# motherboard.net
KiCad netlist of a schematic drawn in EAGLE
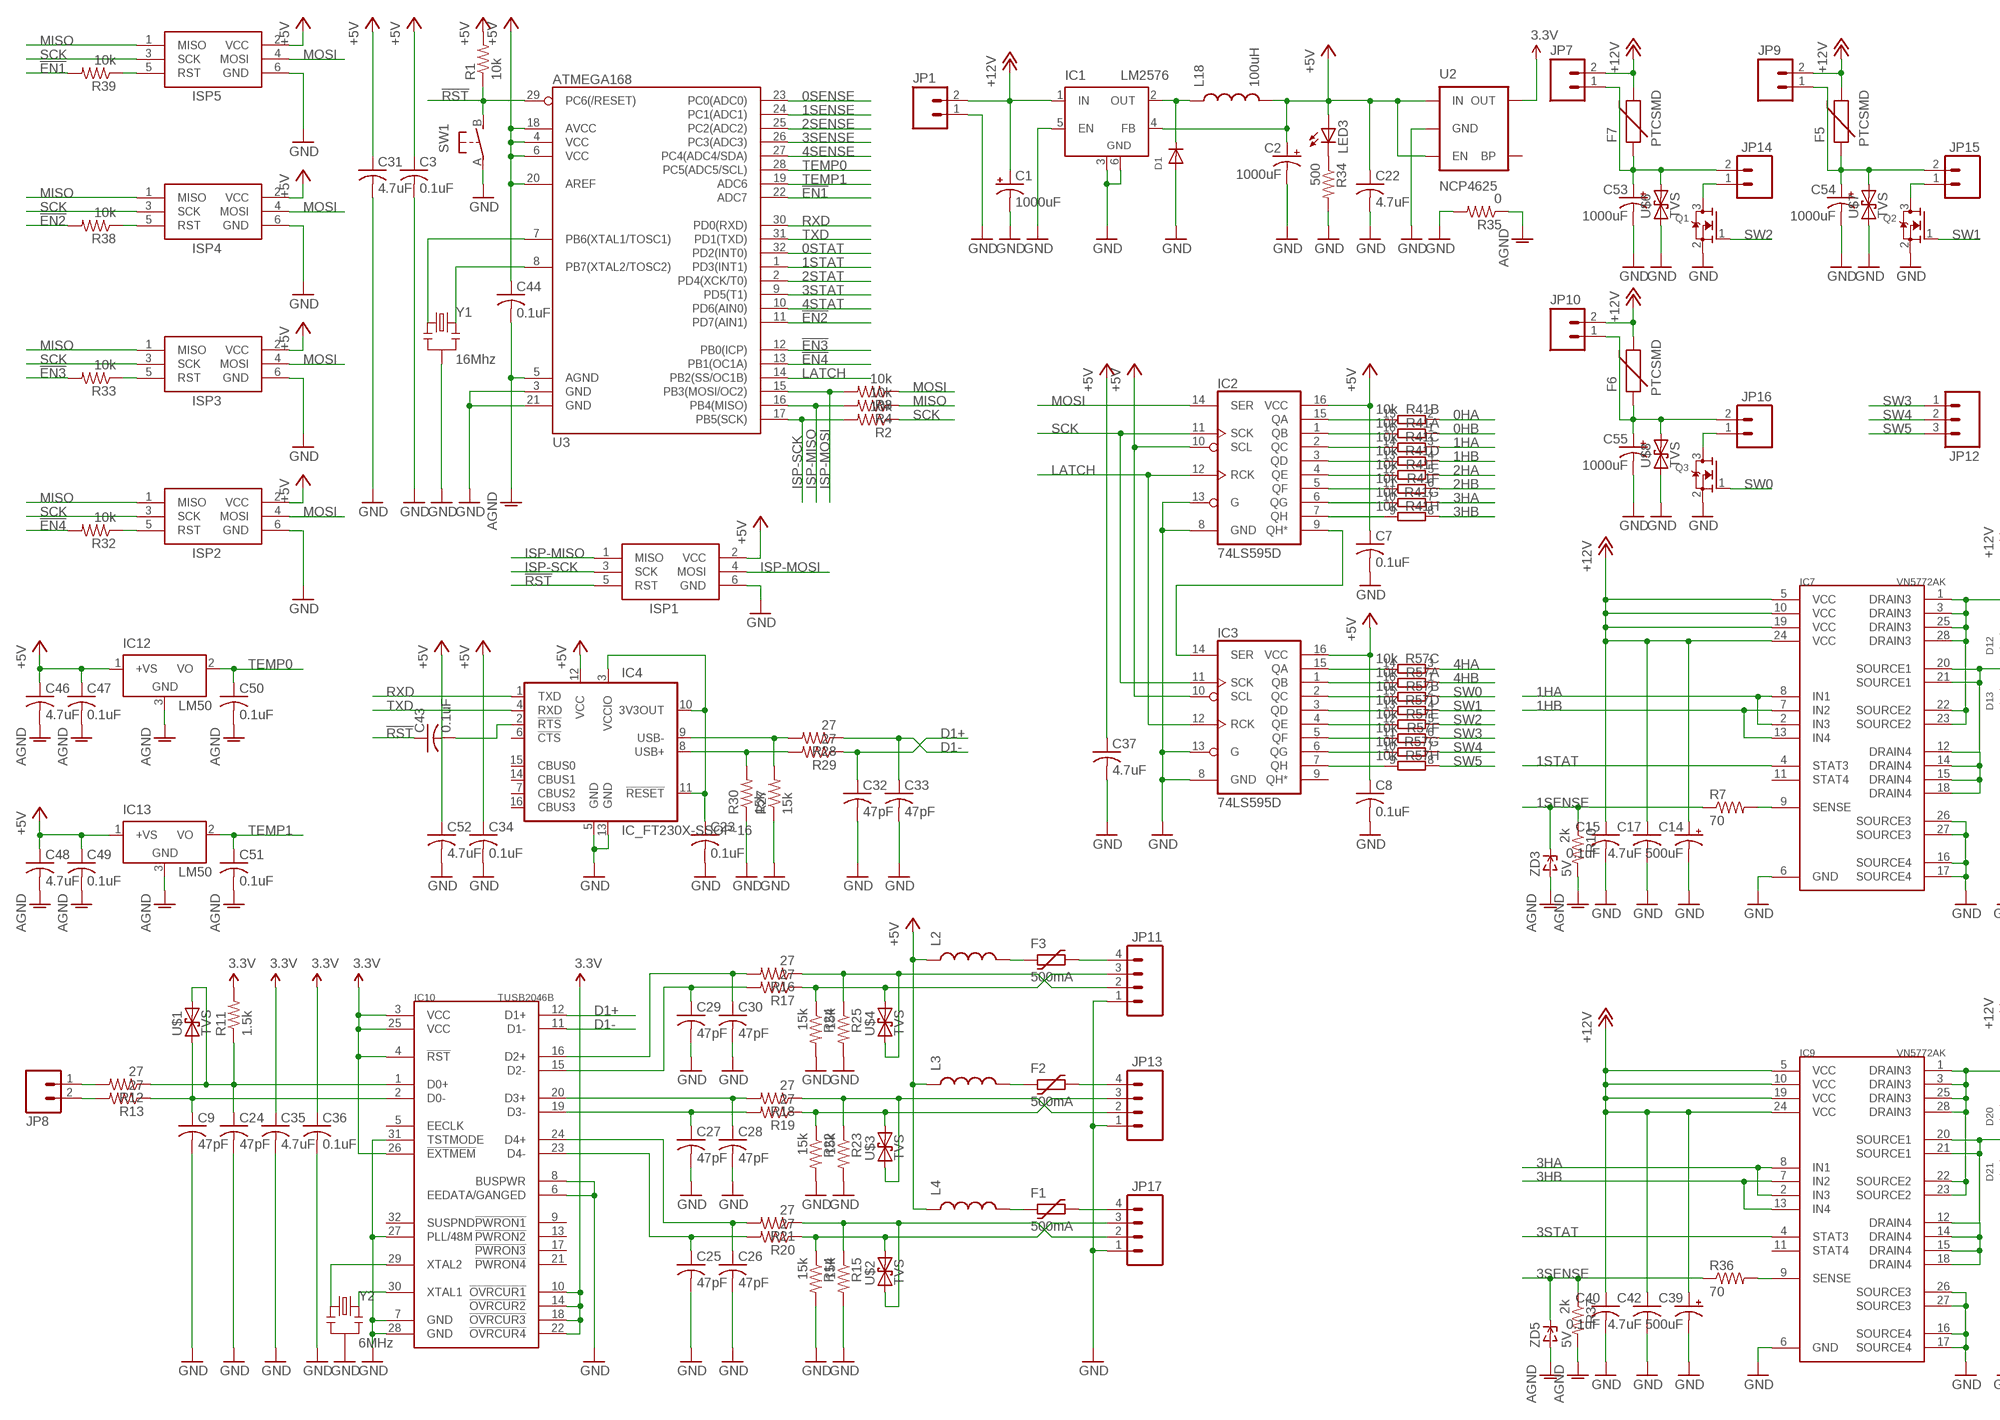
[diagram p0: schematic, sheet 1, part 1 of 2]
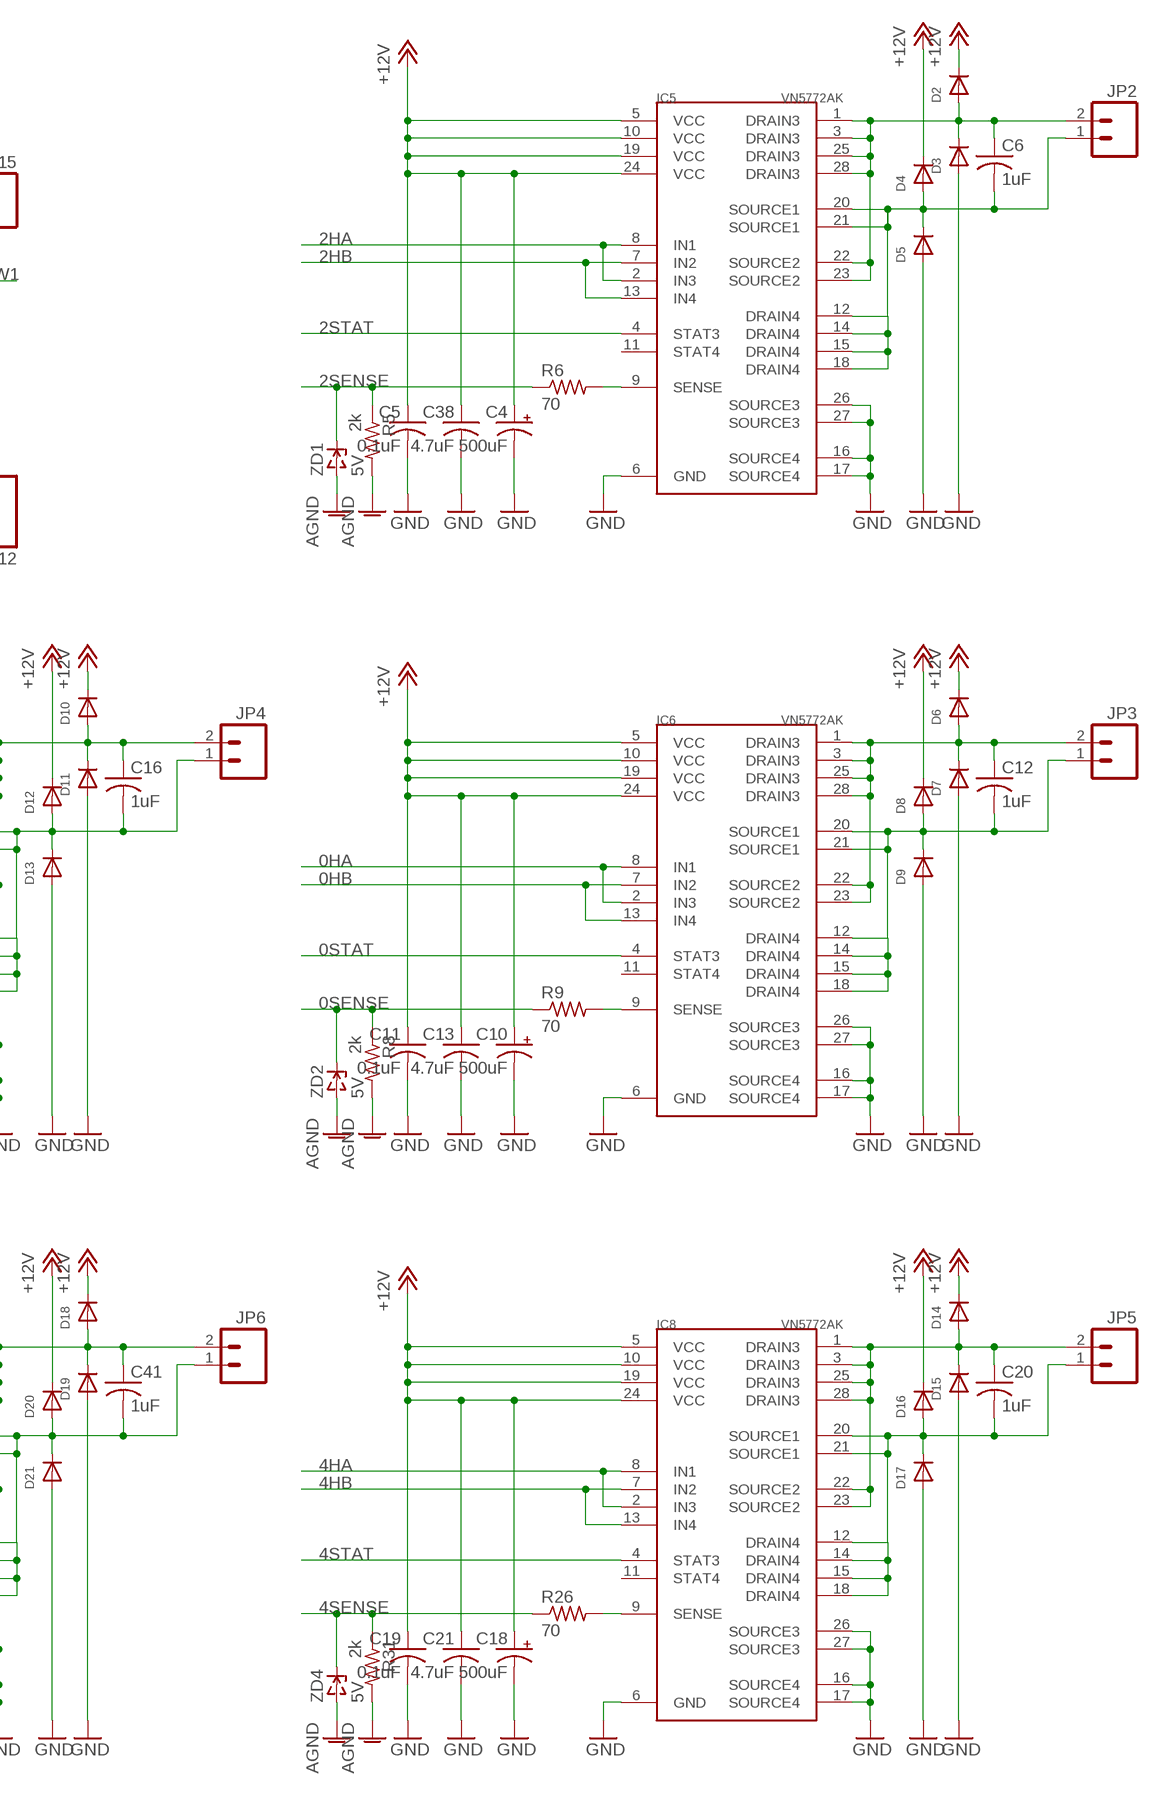
[diagram p1: schematic, sheet 1, part 2 of 2]

(export (version "E")
  (design (tool "Eeschema 10.0.6"))
  (components
    (comp (ref "C1")
      (value "1000uF")
      (footprint "eagle-import:153CLV-0807")
      (libsource (lib "eagle-import") (part "CPOL-US153CLV-0807"))
    )
    (comp (ref "C2")
      (value "1000uF")
      (footprint "eagle-import:153CLV-0807")
      (libsource (lib "eagle-import") (part "CPOL-US153CLV-0807"))
    )
    (comp (ref "C3")
      (value "0.1uF")
      (footprint "eagle-import:C1206")
      (libsource (lib "eagle-import") (part "C-USC1206"))
    )
    (comp (ref "C4")
      (value "500uF")
      (footprint "eagle-import:153CLV-0807")
      (libsource (lib "eagle-import") (part "CPOL-US153CLV-0807"))
    )
    (comp (ref "C5")
      (value "0.1uF")
      (footprint "eagle-import:C1206")
      (libsource (lib "eagle-import") (part "C-USC1206"))
    )
    (comp (ref "C6")
      (value "1uF")
      (footprint "eagle-import:C1206")
      (libsource (lib "eagle-import") (part "C-USC1206"))
    )
    (comp (ref "C7")
      (value "0.1uF")
      (footprint "eagle-import:C1206")
      (libsource (lib "eagle-import") (part "C-USC1206"))
    )
    (comp (ref "C8")
      (value "0.1uF")
      (footprint "eagle-import:C1206")
      (libsource (lib "eagle-import") (part "C-USC1206"))
    )
    (comp (ref "C9")
      (value "47pF")
      (footprint "eagle-import:C1206")
      (libsource (lib "eagle-import") (part "C-USC1206"))
    )
    (comp (ref "C10")
      (value "500uF")
      (footprint "eagle-import:153CLV-0807")
      (libsource (lib "eagle-import") (part "CPOL-US153CLV-0807"))
    )
    (comp (ref "C11")
      (value "0.1uF")
      (footprint "eagle-import:C1206")
      (libsource (lib "eagle-import") (part "C-USC1206"))
    )
    (comp (ref "C12")
      (value "1uF")
      (footprint "eagle-import:C1206")
      (libsource (lib "eagle-import") (part "C-USC1206"))
    )
    (comp (ref "C13")
      (value "4.7uF")
      (footprint "eagle-import:C1206")
      (libsource (lib "eagle-import") (part "C-USC1206"))
    )
    (comp (ref "C14")
      (value "500uF")
      (footprint "eagle-import:153CLV-0807")
      (libsource (lib "eagle-import") (part "CPOL-US153CLV-0807"))
    )
    (comp (ref "C15")
      (value "0.1uF")
      (footprint "eagle-import:C1206")
      (libsource (lib "eagle-import") (part "C-USC1206"))
    )
    (comp (ref "C16")
      (value "1uF")
      (footprint "eagle-import:C1206")
      (libsource (lib "eagle-import") (part "C-USC1206"))
    )
    (comp (ref "C17")
      (value "4.7uF")
      (footprint "eagle-import:C1206")
      (libsource (lib "eagle-import") (part "C-USC1206"))
    )
    (comp (ref "C18")
      (value "500uF")
      (footprint "eagle-import:153CLV-0807")
      (libsource (lib "eagle-import") (part "CPOL-US153CLV-0807"))
    )
    (comp (ref "C19")
      (value "0.1uF")
      (footprint "eagle-import:C1206")
      (libsource (lib "eagle-import") (part "C-USC1206"))
    )
    (comp (ref "C20")
      (value "1uF")
      (footprint "eagle-import:C1206")
      (libsource (lib "eagle-import") (part "C-USC1206"))
    )
    (comp (ref "C21")
      (value "4.7uF")
      (footprint "eagle-import:C1206")
      (libsource (lib "eagle-import") (part "C-USC1206"))
    )
    (comp (ref "C22")
      (value "4.7uF")
      (footprint "eagle-import:C1206")
      (libsource (lib "eagle-import") (part "C-USC1206"))
    )
    (comp (ref "C23")
      (value "0.1uF")
      (footprint "eagle-import:C1206")
      (libsource (lib "eagle-import") (part "C-USC1206"))
    )
    (comp (ref "C24")
      (value "47pF")
      (footprint "eagle-import:C1206")
      (libsource (lib "eagle-import") (part "C-USC1206"))
    )
    (comp (ref "C25")
      (value "47pF")
      (footprint "eagle-import:C1206")
      (libsource (lib "eagle-import") (part "C-USC1206"))
    )
    (comp (ref "C26")
      (value "47pF")
      (footprint "eagle-import:C1206")
      (libsource (lib "eagle-import") (part "C-USC1206"))
    )
    (comp (ref "C27")
      (value "47pF")
      (footprint "eagle-import:C1206")
      (libsource (lib "eagle-import") (part "C-USC1206"))
    )
    (comp (ref "C28")
      (value "47pF")
      (footprint "eagle-import:C1206")
      (libsource (lib "eagle-import") (part "C-USC1206"))
    )
    (comp (ref "C29")
      (value "47pF")
      (footprint "eagle-import:C1206")
      (libsource (lib "eagle-import") (part "C-USC1206"))
    )
    (comp (ref "C30")
      (value "47pF")
      (footprint "eagle-import:C1206")
      (libsource (lib "eagle-import") (part "C-USC1206"))
    )
    (comp (ref "C31")
      (value "4.7uF")
      (footprint "eagle-import:C1206")
      (libsource (lib "eagle-import") (part "C-USC1206"))
    )
    (comp (ref "C32")
      (value "47pF")
      (footprint "eagle-import:C1206")
      (libsource (lib "eagle-import") (part "C-USC1206"))
    )
    (comp (ref "C33")
      (value "47pF")
      (footprint "eagle-import:C1206")
      (libsource (lib "eagle-import") (part "C-USC1206"))
    )
    (comp (ref "C34")
      (value "0.1uF")
      (footprint "eagle-import:C1206")
      (libsource (lib "eagle-import") (part "C-USC1206"))
    )
    (comp (ref "C35")
      (value "4.7uF")
      (footprint "eagle-import:C1206")
      (libsource (lib "eagle-import") (part "C-USC1206"))
    )
    (comp (ref "C36")
      (value "0.1uF")
      (footprint "eagle-import:C1206")
      (libsource (lib "eagle-import") (part "C-USC1206"))
    )
    (comp (ref "C37")
      (value "4.7uF")
      (footprint "eagle-import:C1206")
      (libsource (lib "eagle-import") (part "C-USC1206"))
    )
    (comp (ref "C38")
      (value "4.7uF")
      (footprint "eagle-import:C1206")
      (libsource (lib "eagle-import") (part "C-USC1206"))
    )
    (comp (ref "C39")
      (value "500uF")
      (footprint "eagle-import:153CLV-0807")
      (libsource (lib "eagle-import") (part "CPOL-US153CLV-0807"))
    )
    (comp (ref "C40")
      (value "0.1uF")
      (footprint "eagle-import:C1206")
      (libsource (lib "eagle-import") (part "C-USC1206"))
    )
    (comp (ref "C41")
      (value "1uF")
      (footprint "eagle-import:C1206")
      (libsource (lib "eagle-import") (part "C-USC1206"))
    )
    (comp (ref "C42")
      (value "4.7uF")
      (footprint "eagle-import:C1206")
      (libsource (lib "eagle-import") (part "C-USC1206"))
    )
    (comp (ref "C43")
      (value "0.1uF")
      (footprint "eagle-import:C1206")
      (libsource (lib "eagle-import") (part "C-USC1206"))
    )
    (comp (ref "C44")
      (value "0.1uF")
      (footprint "eagle-import:C1206")
      (libsource (lib "eagle-import") (part "C-USC1206"))
    )
    (comp (ref "C46")
      (value "4.7uF")
      (footprint "eagle-import:C1206")
      (libsource (lib "eagle-import") (part "C-USC1206"))
    )
    (comp (ref "C47")
      (value "0.1uF")
      (footprint "eagle-import:C1206")
      (libsource (lib "eagle-import") (part "C-USC1206"))
    )
    (comp (ref "C48")
      (value "4.7uF")
      (footprint "eagle-import:C1206")
      (libsource (lib "eagle-import") (part "C-USC1206"))
    )
    (comp (ref "C49")
      (value "0.1uF")
      (footprint "eagle-import:C1206")
      (libsource (lib "eagle-import") (part "C-USC1206"))
    )
    (comp (ref "C50")
      (value "0.1uF")
      (footprint "eagle-import:C1206")
      (libsource (lib "eagle-import") (part "C-USC1206"))
    )
    (comp (ref "C51")
      (value "0.1uF")
      (footprint "eagle-import:C1206")
      (libsource (lib "eagle-import") (part "C-USC1206"))
    )
    (comp (ref "C52")
      (value "4.7uF")
      (footprint "eagle-import:C1206")
      (libsource (lib "eagle-import") (part "C-USC1206"))
    )
    (comp (ref "C53")
      (value "1000uF")
      (footprint "eagle-import:153CLV-0807")
      (libsource (lib "eagle-import") (part "CPOL-US153CLV-0807"))
    )
    (comp (ref "C54")
      (value "1000uF")
      (footprint "eagle-import:153CLV-0807")
      (libsource (lib "eagle-import") (part "CPOL-US153CLV-0807"))
    )
    (comp (ref "C55")
      (value "1000uF")
      (footprint "eagle-import:153CLV-0807")
      (libsource (lib "eagle-import") (part "CPOL-US153CLV-0807"))
    )
    (comp (ref "D1")
      (value "DIODESMA")
      (footprint "eagle-import:SMADIODE")
      (libsource (lib "eagle-import") (part "DIODESMA"))
    )
    (comp (ref "D2")
      (value "DIODESOD-123")
      (footprint "eagle-import:SOD-123")
      (libsource (lib "eagle-import") (part "DIODESOD-123"))
    )
    (comp (ref "D3")
      (value "DIODESOD-123")
      (footprint "eagle-import:SOD-123")
      (libsource (lib "eagle-import") (part "DIODESOD-123"))
    )
    (comp (ref "D4")
      (value "DIODESOD-123")
      (footprint "eagle-import:SOD-123")
      (libsource (lib "eagle-import") (part "DIODESOD-123"))
    )
    (comp (ref "D5")
      (value "DIODESOD-123")
      (footprint "eagle-import:SOD-123")
      (libsource (lib "eagle-import") (part "DIODESOD-123"))
    )
    (comp (ref "D6")
      (value "DIODESOD-123")
      (footprint "eagle-import:SOD-123")
      (libsource (lib "eagle-import") (part "DIODESOD-123"))
    )
    (comp (ref "D7")
      (value "DIODESOD-123")
      (footprint "eagle-import:SOD-123")
      (libsource (lib "eagle-import") (part "DIODESOD-123"))
    )
    (comp (ref "D8")
      (value "DIODESOD-123")
      (footprint "eagle-import:SOD-123")
      (libsource (lib "eagle-import") (part "DIODESOD-123"))
    )
    (comp (ref "D9")
      (value "DIODESOD-123")
      (footprint "eagle-import:SOD-123")
      (libsource (lib "eagle-import") (part "DIODESOD-123"))
    )
    (comp (ref "D10")
      (value "DIODESOD-123")
      (footprint "eagle-import:SOD-123")
      (libsource (lib "eagle-import") (part "DIODESOD-123"))
    )
    (comp (ref "D11")
      (value "DIODESOD-123")
      (footprint "eagle-import:SOD-123")
      (libsource (lib "eagle-import") (part "DIODESOD-123"))
    )
    (comp (ref "D12")
      (value "DIODESOD-123")
      (footprint "eagle-import:SOD-123")
      (libsource (lib "eagle-import") (part "DIODESOD-123"))
    )
    (comp (ref "D13")
      (value "DIODESOD-123")
      (footprint "eagle-import:SOD-123")
      (libsource (lib "eagle-import") (part "DIODESOD-123"))
    )
    (comp (ref "D14")
      (value "DIODESOD-123")
      (footprint "eagle-import:SOD-123")
      (libsource (lib "eagle-import") (part "DIODESOD-123"))
    )
    (comp (ref "D15")
      (value "DIODESOD-123")
      (footprint "eagle-import:SOD-123")
      (libsource (lib "eagle-import") (part "DIODESOD-123"))
    )
    (comp (ref "D16")
      (value "DIODESOD-123")
      (footprint "eagle-import:SOD-123")
      (libsource (lib "eagle-import") (part "DIODESOD-123"))
    )
    (comp (ref "D17")
      (value "DIODESOD-123")
      (footprint "eagle-import:SOD-123")
      (libsource (lib "eagle-import") (part "DIODESOD-123"))
    )
    (comp (ref "D18")
      (value "DIODESOD-123")
      (footprint "eagle-import:SOD-123")
      (libsource (lib "eagle-import") (part "DIODESOD-123"))
    )
    (comp (ref "D19")
      (value "DIODESOD-123")
      (footprint "eagle-import:SOD-123")
      (libsource (lib "eagle-import") (part "DIODESOD-123"))
    )
    (comp (ref "D20")
      (value "DIODESOD-123")
      (footprint "eagle-import:SOD-123")
      (libsource (lib "eagle-import") (part "DIODESOD-123"))
    )
    (comp (ref "D21")
      (value "DIODESOD-123")
      (footprint "eagle-import:SOD-123")
      (libsource (lib "eagle-import") (part "DIODESOD-123"))
    )
    (comp (ref "F1")
      (value "500mA")
      (footprint "eagle-import:PTC1812L")
      (libsource (lib "eagle-import") (part "FUSE_PTC-1812"))
    )
    (comp (ref "F2")
      (value "500mA")
      (footprint "eagle-import:PTC1812L")
      (libsource (lib "eagle-import") (part "FUSE_PTC-1812"))
    )
    (comp (ref "F3")
      (value "500mA")
      (footprint "eagle-import:PTC1812L")
      (libsource (lib "eagle-import") (part "FUSE_PTC-1812"))
    )
    (comp (ref "F5")
      (value "PTCSMD")
      (footprint "eagle-import:PTC-1206")
      (libsource (lib "eagle-import") (part "PTCSMD"))
    )
    (comp (ref "F6")
      (value "PTCSMD")
      (footprint "eagle-import:PTC-1206")
      (libsource (lib "eagle-import") (part "PTCSMD"))
    )
    (comp (ref "F7")
      (value "PTCSMD")
      (footprint "eagle-import:PTC-1206")
      (libsource (lib "eagle-import") (part "PTCSMD"))
    )
    (comp (ref "IC1")
      (value "LM2576")
      (footprint "eagle-import:TO263-5")
      (libsource (lib "eagle-import") (part "LM2596S"))
    )
    (comp (ref "IC2")
      (value "74LS595D")
      (footprint "eagle-import:SO16")
      (libsource (lib "eagle-import") (part "74595DLS"))
    )
    (comp (ref "IC3")
      (value "74LS595D")
      (footprint "eagle-import:SO16")
      (libsource (lib "eagle-import") (part "74595DLS"))
    )
    (comp (ref "IC4")
      (value "IC_FT230X-SSOP-16")
      (footprint "eagle-import:SSOP-16-FTDI")
      (libsource (lib "eagle-import") (part "IC_FT230X-SSOP-16"))
    )
    (comp (ref "IC5")
      (value "VN5772AK")
      (footprint "eagle-import:SO-28")
      (libsource (lib "eagle-import") (part "VN5772AK"))
    )
    (comp (ref "IC6")
      (value "VN5772AK")
      (footprint "eagle-import:SO-28")
      (libsource (lib "eagle-import") (part "VN5772AK"))
    )
    (comp (ref "IC7")
      (value "VN5772AK")
      (footprint "eagle-import:SO-28")
      (libsource (lib "eagle-import") (part "VN5772AK"))
    )
    (comp (ref "IC8")
      (value "VN5772AK")
      (footprint "eagle-import:SO-28")
      (libsource (lib "eagle-import") (part "VN5772AK"))
    )
    (comp (ref "IC9")
      (value "VN5772AK")
      (footprint "eagle-import:SO-28")
      (libsource (lib "eagle-import") (part "VN5772AK"))
    )
    (comp (ref "IC10")
      (value "TUSB2046B")
      (footprint "eagle-import:LQFP-32")
      (libsource (lib "eagle-import") (part "TUSB2046B"))
    )
    (comp (ref "IC12")
      (value "LM50")
      (footprint "eagle-import:SOT23")
      (libsource (lib "eagle-import") (part "LM50"))
    )
    (comp (ref "IC13")
      (value "LM50")
      (footprint "eagle-import:SOT23")
      (libsource (lib "eagle-import") (part "LM50"))
    )
    (comp (ref "ISP1")
      (value "AVRISP-6")
      (footprint "eagle-import:AVRISP")
      (libsource (lib "eagle-import") (part "AVRISP-6"))
    )
    (comp (ref "ISP2")
      (value "AVRISP-6")
      (footprint "eagle-import:AVRISP")
      (libsource (lib "eagle-import") (part "AVRISP-6"))
    )
    (comp (ref "ISP3")
      (value "AVRISP-6")
      (footprint "eagle-import:AVRISP")
      (libsource (lib "eagle-import") (part "AVRISP-6"))
    )
    (comp (ref "ISP4")
      (value "AVRISP-6")
      (footprint "eagle-import:AVRISP")
      (libsource (lib "eagle-import") (part "AVRISP-6"))
    )
    (comp (ref "ISP5")
      (value "AVRISP-6")
      (footprint "eagle-import:AVRISP")
      (libsource (lib "eagle-import") (part "AVRISP-6"))
    )
    (comp (ref "JP1")
      (value "M023.5MM")
      (footprint "eagle-import:SCREWTERMINAL-3.5MM-2")
      (libsource (lib "eagle-import") (part "M023.5MM"))
    )
    (comp (ref "JP2")
      (value "M023.5MM")
      (footprint "eagle-import:SCREWTERMINAL-3.5MM-2")
      (libsource (lib "eagle-import") (part "M023.5MM"))
    )
    (comp (ref "JP3")
      (value "M023.5MM")
      (footprint "eagle-import:SCREWTERMINAL-3.5MM-2")
      (libsource (lib "eagle-import") (part "M023.5MM"))
    )
    (comp (ref "JP4")
      (value "M023.5MM")
      (footprint "eagle-import:SCREWTERMINAL-3.5MM-2")
      (libsource (lib "eagle-import") (part "M023.5MM"))
    )
    (comp (ref "JP5")
      (value "M023.5MM")
      (footprint "eagle-import:SCREWTERMINAL-3.5MM-2")
      (libsource (lib "eagle-import") (part "M023.5MM"))
    )
    (comp (ref "JP6")
      (value "M023.5MM")
      (footprint "eagle-import:SCREWTERMINAL-3.5MM-2")
      (libsource (lib "eagle-import") (part "M023.5MM"))
    )
    (comp (ref "JP7")
      (value "M02PTH")
      (footprint "eagle-import:1X02")
      (libsource (lib "eagle-import") (part "M02PTH"))
    )
    (comp (ref "JP8")
      (value "M023.5MM")
      (footprint "eagle-import:SCREWTERMINAL-3.5MM-2")
      (libsource (lib "eagle-import") (part "M023.5MM"))
    )
    (comp (ref "JP9")
      (value "M02PTH")
      (footprint "eagle-import:1X02")
      (libsource (lib "eagle-import") (part "M02PTH"))
    )
    (comp (ref "JP10")
      (value "M02PTH")
      (footprint "eagle-import:1X02")
      (libsource (lib "eagle-import") (part "M02PTH"))
    )
    (comp (ref "JP11")
      (value "M04SCREW")
      (footprint "eagle-import:SCREWTERMINAL-3.5MM-4")
      (libsource (lib "eagle-import") (part "M04SCREW"))
    )
    (comp (ref "JP12")
      (value "M03PTH")
      (footprint "eagle-import:1X03")
      (libsource (lib "eagle-import") (part "M03PTH"))
    )
    (comp (ref "JP13")
      (value "M04SCREW")
      (footprint "eagle-import:SCREWTERMINAL-3.5MM-4")
      (libsource (lib "eagle-import") (part "M04SCREW"))
    )
    (comp (ref "JP14")
      (value "M023.5MM")
      (footprint "eagle-import:SCREWTERMINAL-3.5MM-2")
      (libsource (lib "eagle-import") (part "M023.5MM"))
    )
    (comp (ref "JP15")
      (value "M023.5MM")
      (footprint "eagle-import:SCREWTERMINAL-3.5MM-2")
      (libsource (lib "eagle-import") (part "M023.5MM"))
    )
    (comp (ref "JP16")
      (value "M023.5MM")
      (footprint "eagle-import:SCREWTERMINAL-3.5MM-2")
      (libsource (lib "eagle-import") (part "M023.5MM"))
    )
    (comp (ref "JP17")
      (value "M04SCREW")
      (footprint "eagle-import:SCREWTERMINAL-3.5MM-4")
      (libsource (lib "eagle-import") (part "M04SCREW"))
    )
    (comp (ref "L2")
      (value "INDUCTOR1206H*")
      (footprint "eagle-import:INDUCTOR-1206")
      (libsource (lib "eagle-import") (part "INDUCTORH1206"))
    )
    (comp (ref "L3")
      (value "INDUCTOR1206H*")
      (footprint "eagle-import:INDUCTOR-1206")
      (libsource (lib "eagle-import") (part "INDUCTORH1206"))
    )
    (comp (ref "L4")
      (value "INDUCTOR1206H*")
      (footprint "eagle-import:INDUCTOR-1206")
      (libsource (lib "eagle-import") (part "INDUCTORH1206"))
    )
    (comp (ref "L18")
      (value "100uH")
      (footprint "eagle-import:CDRH125")
      (libsource (lib "eagle-import") (part "INDUCTORPWR"))
    )
    (comp (ref "LED3")
      (value "LEDCHIPLED_1206")
      (footprint "eagle-import:CHIPLED_1206")
      (libsource (lib "eagle-import") (part "LEDCHIPLED_1206"))
    )
    (comp (ref "Q1")
      (value "MOSFET-NREFLOW")
      (footprint "eagle-import:SOT23")
      (libsource (lib "eagle-import") (part "MOSFET-NREFLOW"))
    )
    (comp (ref "Q2")
      (value "MOSFET-NREFLOW")
      (footprint "eagle-import:SOT23")
      (libsource (lib "eagle-import") (part "MOSFET-NREFLOW"))
    )
    (comp (ref "Q3")
      (value "MOSFET-NREFLOW")
      (footprint "eagle-import:SOT23")
      (libsource (lib "eagle-import") (part "MOSFET-NREFLOW"))
    )
    (comp (ref "R1")
      (value "10k")
      (footprint "eagle-import:R1206")
      (libsource (lib "eagle-import") (part "R-US_R1206"))
    )
    (comp (ref "R2")
      (value "10k")
      (footprint "eagle-import:R1206")
      (libsource (lib "eagle-import") (part "R-US_R1206"))
    )
    (comp (ref "R3")
      (value "10k")
      (footprint "eagle-import:R1206")
      (libsource (lib "eagle-import") (part "R-US_R1206"))
    )
    (comp (ref "R4")
      (value "10k")
      (footprint "eagle-import:R1206")
      (libsource (lib "eagle-import") (part "R-US_R1206"))
    )
    (comp (ref "R5")
      (value "2k")
      (footprint "eagle-import:R1206")
      (libsource (lib "eagle-import") (part "R-US_R1206"))
    )
    (comp (ref "R6")
      (value "70")
      (footprint "eagle-import:R1206")
      (libsource (lib "eagle-import") (part "R-US_R1206"))
    )
    (comp (ref "R7")
      (value "70")
      (footprint "eagle-import:R1206")
      (libsource (lib "eagle-import") (part "R-US_R1206"))
    )
    (comp (ref "R8")
      (value "2k")
      (footprint "eagle-import:R1206")
      (libsource (lib "eagle-import") (part "R-US_R1206"))
    )
    (comp (ref "R9")
      (value "70")
      (footprint "eagle-import:R1206")
      (libsource (lib "eagle-import") (part "R-US_R1206"))
    )
    (comp (ref "R10")
      (value "2k")
      (footprint "eagle-import:R1206")
      (libsource (lib "eagle-import") (part "R-US_R1206"))
    )
    (comp (ref "R11")
      (value "1.5k")
      (footprint "eagle-import:R1206")
      (libsource (lib "eagle-import") (part "R-US_R1206"))
    )
    (comp (ref "R12")
      (value "27")
      (footprint "eagle-import:R1206")
      (libsource (lib "eagle-import") (part "R-US_R1206"))
    )
    (comp (ref "R13")
      (value "27")
      (footprint "eagle-import:R1206")
      (libsource (lib "eagle-import") (part "R-US_R1206"))
    )
    (comp (ref "R14")
      (value "15k")
      (footprint "eagle-import:R1206")
      (libsource (lib "eagle-import") (part "R-US_R1206"))
    )
    (comp (ref "R15")
      (value "15k")
      (footprint "eagle-import:R1206")
      (libsource (lib "eagle-import") (part "R-US_R1206"))
    )
    (comp (ref "R16")
      (value "27")
      (footprint "eagle-import:R1206")
      (libsource (lib "eagle-import") (part "R-US_R1206"))
    )
    (comp (ref "R17")
      (value "27")
      (footprint "eagle-import:R1206")
      (libsource (lib "eagle-import") (part "R-US_R1206"))
    )
    (comp (ref "R18")
      (value "27")
      (footprint "eagle-import:R1206")
      (libsource (lib "eagle-import") (part "R-US_R1206"))
    )
    (comp (ref "R19")
      (value "27")
      (footprint "eagle-import:R1206")
      (libsource (lib "eagle-import") (part "R-US_R1206"))
    )
    (comp (ref "R20")
      (value "27")
      (footprint "eagle-import:R1206")
      (libsource (lib "eagle-import") (part "R-US_R1206"))
    )
    (comp (ref "R21")
      (value "27")
      (footprint "eagle-import:R1206")
      (libsource (lib "eagle-import") (part "R-US_R1206"))
    )
    (comp (ref "R22")
      (value "15k")
      (footprint "eagle-import:R1206")
      (libsource (lib "eagle-import") (part "R-US_R1206"))
    )
    (comp (ref "R23")
      (value "15k")
      (footprint "eagle-import:R1206")
      (libsource (lib "eagle-import") (part "R-US_R1206"))
    )
    (comp (ref "R24")
      (value "15k")
      (footprint "eagle-import:R1206")
      (libsource (lib "eagle-import") (part "R-US_R1206"))
    )
    (comp (ref "R25")
      (value "15k")
      (footprint "eagle-import:R1206")
      (libsource (lib "eagle-import") (part "R-US_R1206"))
    )
    (comp (ref "R26")
      (value "70")
      (footprint "eagle-import:R1206")
      (libsource (lib "eagle-import") (part "R-US_R1206"))
    )
    (comp (ref "R27")
      (value "15k")
      (footprint "eagle-import:R1206")
      (libsource (lib "eagle-import") (part "R-US_R1206"))
    )
    (comp (ref "R28")
      (value "27")
      (footprint "eagle-import:R1206")
      (libsource (lib "eagle-import") (part "R-US_R1206"))
    )
    (comp (ref "R29")
      (value "27")
      (footprint "eagle-import:R1206")
      (libsource (lib "eagle-import") (part "R-US_R1206"))
    )
    (comp (ref "R30")
      (value "15k")
      (footprint "eagle-import:R1206")
      (libsource (lib "eagle-import") (part "R-US_R1206"))
    )
    (comp (ref "R31")
      (value "2k")
      (footprint "eagle-import:R1206")
      (libsource (lib "eagle-import") (part "R-US_R1206"))
    )
    (comp (ref "R32")
      (value "10k")
      (footprint "eagle-import:R1206")
      (libsource (lib "eagle-import") (part "R-US_R1206"))
    )
    (comp (ref "R33")
      (value "10k")
      (footprint "eagle-import:R1206")
      (libsource (lib "eagle-import") (part "R-US_R1206"))
    )
    (comp (ref "R34")
      (value "500")
      (footprint "eagle-import:R1206")
      (libsource (lib "eagle-import") (part "R-US_R1206"))
    )
    (comp (ref "R35")
      (value "0")
      (footprint "eagle-import:R1206")
      (libsource (lib "eagle-import") (part "R-US_R1206"))
    )
    (comp (ref "R36")
      (value "70")
      (footprint "eagle-import:R1206")
      (libsource (lib "eagle-import") (part "R-US_R1206"))
    )
    (comp (ref "R37")
      (value "2k")
      (footprint "eagle-import:R1206")
      (libsource (lib "eagle-import") (part "R-US_R1206"))
    )
    (comp (ref "R38")
      (value "10k")
      (footprint "eagle-import:R1206")
      (libsource (lib "eagle-import") (part "R-US_R1206"))
    )
    (comp (ref "R39")
      (value "10k")
      (footprint "eagle-import:R1206")
      (libsource (lib "eagle-import") (part "R-US_R1206"))
    )
    (comp (ref "R41")
      (value "10k")
      (footprint "eagle-import:SO16")
      (libsource (lib "eagle-import") (part "2NBS16-8E"))
    )
    (comp (ref "R57")
      (value "10k")
      (footprint "eagle-import:SO16")
      (libsource (lib "eagle-import") (part "2NBS16-8E"))
    )
    (comp (ref "SW1")
      (value "FSMSM")
      (footprint "eagle-import:FSMSM")
      (libsource (lib "eagle-import") (part "FSMSM"))
    )
    (comp (ref "U$1")
      (value "TVS")
      (footprint "eagle-import:SMA-DIODE")
      (libsource (lib "eagle-import") (part "TVS"))
    )
    (comp (ref "U$2")
      (value "TVS")
      (footprint "eagle-import:SMA-DIODE")
      (libsource (lib "eagle-import") (part "TVS"))
    )
    (comp (ref "U$3")
      (value "TVS")
      (footprint "eagle-import:SMA-DIODE")
      (libsource (lib "eagle-import") (part "TVS"))
    )
    (comp (ref "U$4")
      (value "TVS")
      (footprint "eagle-import:SMA-DIODE")
      (libsource (lib "eagle-import") (part "TVS"))
    )
    (comp (ref "U$6")
      (value "TVS")
      (footprint "eagle-import:SMA-DIODE")
      (libsource (lib "eagle-import") (part "TVS"))
    )
    (comp (ref "U$7")
      (value "TVS")
      (footprint "eagle-import:SMA-DIODE")
      (libsource (lib "eagle-import") (part "TVS"))
    )
    (comp (ref "U$8")
      (value "TVS")
      (footprint "eagle-import:SMA-DIODE")
      (libsource (lib "eagle-import") (part "TVS"))
    )
    (comp (ref "U2")
      (value "NCP4625")
      (footprint "eagle-import:SOT23-5")
      (libsource (lib "eagle-import") (part "V_REG_LDOSMD"))
    )
    (comp (ref "U3")
      (value "ATMEGA168")
      (footprint "eagle-import:TQFP32-08")
      (libsource (lib "eagle-import") (part "ATMEGA168"))
    )
    (comp (ref "Y1")
      (value "16Mhz")
      (footprint "eagle-import:RESONATOR-SMD")
      (libsource (lib "eagle-import") (part "RESONATORSMD"))
    )
    (comp (ref "Y2")
      (value "6MHz")
      (footprint "eagle-import:RESONATOR-SMD")
      (libsource (lib "eagle-import") (part "RESONATORSMD"))
    )
    (comp (ref "ZD1")
      (value "5V")
      (footprint "eagle-import:SOD-123")
      (libsource (lib "eagle-import") (part "ZENERSOD-123"))
    )
    (comp (ref "ZD2")
      (value "5V")
      (footprint "eagle-import:SOD-123")
      (libsource (lib "eagle-import") (part "ZENERSOD-123"))
    )
    (comp (ref "ZD3")
      (value "5V")
      (footprint "eagle-import:SOD-123")
      (libsource (lib "eagle-import") (part "ZENERSOD-123"))
    )
    (comp (ref "ZD4")
      (value "5V")
      (footprint "eagle-import:SOD-123")
      (libsource (lib "eagle-import") (part "ZENERSOD-123"))
    )
    (comp (ref "ZD5")
      (value "5V")
      (footprint "eagle-import:SOD-123")
      (libsource (lib "eagle-import") (part "ZENERSOD-123"))
    )
  )
  (nets
    (net (code "1") (name "+5V") (class "Default")
      (node (ref "C2") (pin "+") (pinfunction "+_+") (pintype "passive"))
      (node (ref "C22") (pin "1") (pinfunction "1_1") (pintype "passive"))
      (node (ref "C3") (pin "1") (pinfunction "1_1") (pintype "passive"))
      (node (ref "C31") (pin "1") (pinfunction "1_1") (pintype "passive"))
      (node (ref "C34") (pin "1") (pinfunction "1_1") (pintype "passive"))
      (node (ref "C37") (pin "1") (pinfunction "1_1") (pintype "passive"))
      (node (ref "C44") (pin "1") (pinfunction "1_1") (pintype "passive"))
      (node (ref "C46") (pin "1") (pinfunction "1_1") (pintype "passive"))
      (node (ref "C47") (pin "1") (pinfunction "1_1") (pintype "passive"))
      (node (ref "C48") (pin "1") (pinfunction "1_1") (pintype "passive"))
      (node (ref "C49") (pin "1") (pinfunction "1_1") (pintype "passive"))
      (node (ref "C52") (pin "1") (pinfunction "1_1") (pintype "passive"))
      (node (ref "C7") (pin "1") (pinfunction "1_1") (pintype "passive"))
      (node (ref "C8") (pin "1") (pinfunction "1_1") (pintype "passive"))
      (node (ref "IC1") (pin "4") (pinfunction "FB_4") (pintype "input"))
      (node (ref "IC12") (pin "1") (pinfunction "+VS_1") (pintype "input"))
      (node (ref "IC13") (pin "1") (pinfunction "+VS_1") (pintype "input"))
      (node (ref "IC2") (pin "10") (pinfunction "SCL_10") (pintype "input"))
      (node (ref "IC2") (pin "16") (pinfunction "VCC_16") (pintype "power_in"))
      (node (ref "IC3") (pin "10") (pinfunction "SCL_10") (pintype "input"))
      (node (ref "IC3") (pin "16") (pinfunction "VCC_16") (pintype "power_in"))
      (node (ref "IC4") (pin "12") (pinfunction "VCC_12") (pintype "power_in"))
      (node (ref "ISP1") (pin "2") (pinfunction "VCC_2") (pintype "power_in"))
      (node (ref "ISP2") (pin "2") (pinfunction "VCC_2") (pintype "power_in"))
      (node (ref "ISP3") (pin "2") (pinfunction "VCC_2") (pintype "power_in"))
      (node (ref "ISP4") (pin "2") (pinfunction "VCC_2") (pintype "power_in"))
      (node (ref "ISP5") (pin "2") (pinfunction "VCC_2") (pintype "power_in"))
      (node (ref "L18") (pin "2") (pinfunction "2_2") (pintype "passive"))
      (node (ref "L2") (pin "P$1") (pinfunction "1_P$1") (pintype "passive"))
      (node (ref "L3") (pin "P$1") (pinfunction "1_P$1") (pintype "passive"))
      (node (ref "L4") (pin "P$1") (pinfunction "1_P$1") (pintype "passive"))
      (node (ref "LED3") (pin "A") (pinfunction "A_A") (pintype "passive"))
      (node (ref "R1") (pin "2") (pinfunction "2_2") (pintype "passive"))
      (node (ref "U2") (pin "1") (pinfunction "IN_1") (pintype "input"))
      (node (ref "U2") (pin "3") (pinfunction "EN_3") (pintype "input"))
      (node (ref "U3") (pin "18") (pinfunction "AVCC_18") (pintype "bidirectional"))
      (node (ref "U3") (pin "20") (pinfunction "AREF_20") (pintype "bidirectional"))
      (node (ref "U3") (pin "4") (pinfunction "VCC_4") (pintype "bidirectional"))
      (node (ref "U3") (pin "6") (pinfunction "VCC_6") (pintype "bidirectional"))
    )
    (net (code "2") (name "+12V") (class "Default")
      (node (ref "C1") (pin "+") (pinfunction "+_+") (pintype "passive"))
      (node (ref "C10") (pin "+") (pinfunction "+_+") (pintype "passive"))
      (node (ref "C11") (pin "1") (pinfunction "1_1") (pintype "passive"))
      (node (ref "C13") (pin "1") (pinfunction "1_1") (pintype "passive"))
      (node (ref "C14") (pin "+") (pinfunction "+_+") (pintype "passive"))
      (node (ref "C15") (pin "1") (pinfunction "1_1") (pintype "passive"))
      (node (ref "C17") (pin "1") (pinfunction "1_1") (pintype "passive"))
      (node (ref "C18") (pin "+") (pinfunction "+_+") (pintype "passive"))
      (node (ref "C19") (pin "1") (pinfunction "1_1") (pintype "passive"))
      (node (ref "C21") (pin "1") (pinfunction "1_1") (pintype "passive"))
      (node (ref "C38") (pin "1") (pinfunction "1_1") (pintype "passive"))
      (node (ref "C39") (pin "+") (pinfunction "+_+") (pintype "passive"))
      (node (ref "C4") (pin "+") (pinfunction "+_+") (pintype "passive"))
      (node (ref "C40") (pin "1") (pinfunction "1_1") (pintype "passive"))
      (node (ref "C42") (pin "1") (pinfunction "1_1") (pintype "passive"))
      (node (ref "C5") (pin "1") (pinfunction "1_1") (pintype "passive"))
      (node (ref "D10") (pin "C") (pinfunction "C_C") (pintype "passive"))
      (node (ref "D12") (pin "C") (pinfunction "C_C") (pintype "passive"))
      (node (ref "D14") (pin "C") (pinfunction "C_C") (pintype "passive"))
      (node (ref "D16") (pin "C") (pinfunction "C_C") (pintype "passive"))
      (node (ref "D18") (pin "C") (pinfunction "C_C") (pintype "passive"))
      (node (ref "D2") (pin "C") (pinfunction "C_C") (pintype "passive"))
      (node (ref "D20") (pin "C") (pinfunction "C_C") (pintype "passive"))
      (node (ref "D4") (pin "C") (pinfunction "C_C") (pintype "passive"))
      (node (ref "D6") (pin "C") (pinfunction "C_C") (pintype "passive"))
      (node (ref "D8") (pin "C") (pinfunction "C_C") (pintype "passive"))
      (node (ref "F5") (pin "2") (pinfunction "2_2") (pintype "bidirectional"))
      (node (ref "F6") (pin "2") (pinfunction "2_2") (pintype "bidirectional"))
      (node (ref "F7") (pin "2") (pinfunction "2_2") (pintype "bidirectional"))
      (node (ref "IC1") (pin "1") (pinfunction "IN_1") (pintype "input"))
      (node (ref "IC5") (pin "10") (pinfunction "VCC_10") (pintype "bidirectional"))
      (node (ref "IC5") (pin "19") (pinfunction "VCC_19") (pintype "bidirectional"))
      (node (ref "IC5") (pin "24") (pinfunction "VCC_24") (pintype "bidirectional"))
      (node (ref "IC5") (pin "5") (pinfunction "VCC_5") (pintype "bidirectional"))
      (node (ref "IC6") (pin "10") (pinfunction "VCC_10") (pintype "bidirectional"))
      (node (ref "IC6") (pin "19") (pinfunction "VCC_19") (pintype "bidirectional"))
      (node (ref "IC6") (pin "24") (pinfunction "VCC_24") (pintype "bidirectional"))
      (node (ref "IC6") (pin "5") (pinfunction "VCC_5") (pintype "bidirectional"))
      (node (ref "IC7") (pin "10") (pinfunction "VCC_10") (pintype "bidirectional"))
      (node (ref "IC7") (pin "19") (pinfunction "VCC_19") (pintype "bidirectional"))
      (node (ref "IC7") (pin "24") (pinfunction "VCC_24") (pintype "bidirectional"))
      (node (ref "IC7") (pin "5") (pinfunction "VCC_5") (pintype "bidirectional"))
      (node (ref "IC8") (pin "10") (pinfunction "VCC_10") (pintype "bidirectional"))
      (node (ref "IC8") (pin "19") (pinfunction "VCC_19") (pintype "bidirectional"))
      (node (ref "IC8") (pin "24") (pinfunction "VCC_24") (pintype "bidirectional"))
      (node (ref "IC8") (pin "5") (pinfunction "VCC_5") (pintype "bidirectional"))
      (node (ref "IC9") (pin "10") (pinfunction "VCC_10") (pintype "bidirectional"))
      (node (ref "IC9") (pin "19") (pinfunction "VCC_19") (pintype "bidirectional"))
      (node (ref "IC9") (pin "24") (pinfunction "VCC_24") (pintype "bidirectional"))
      (node (ref "IC9") (pin "5") (pinfunction "VCC_5") (pintype "bidirectional"))
      (node (ref "JP1") (pin "2") (pinfunction "2_2") (pintype "passive"))
      (node (ref "JP10") (pin "2") (pinfunction "2_2") (pintype "passive"))
      (node (ref "JP7") (pin "2") (pinfunction "2_2") (pintype "passive"))
      (node (ref "JP9") (pin "2") (pinfunction "2_2") (pintype "passive"))
    )
    (net (code "3") (name "/0HA") (class "Default")
      (node (ref "IC6") (pin "2") (pinfunction "IN3_2") (pintype "bidirectional"))
      (node (ref "IC6") (pin "8") (pinfunction "IN1_8") (pintype "bidirectional"))
      (node (ref "R41") (pin "2") (pinfunction "1_2") (pintype "passive"))
    )
    (net (code "4") (name "/0HB") (class "Default")
      (node (ref "IC6") (pin "13") (pinfunction "IN4_13") (pintype "bidirectional"))
      (node (ref "IC6") (pin "7") (pinfunction "IN2_7") (pintype "bidirectional"))
      (node (ref "R41") (pin "1") (pinfunction "1_1") (pintype "passive"))
    )
    (net (code "5") (name "/0SENSE") (class "Default")
      (node (ref "R8") (pin "1") (pinfunction "1_1") (pintype "passive"))
      (node (ref "R9") (pin "1") (pinfunction "1_1") (pintype "passive"))
      (node (ref "U3") (pin "23") (pinfunction "PC0(ADC0)_23") (pintype "bidirectional"))
      (node (ref "ZD2") (pin "C") (pinfunction "C_C") (pintype "passive"))
    )
    (net (code "6") (name "/0STAT") (class "Default")
      (node (ref "IC6") (pin "4") (pinfunction "STAT3_4") (pintype "bidirectional"))
      (node (ref "U3") (pin "32") (pinfunction "PD2(INT0)_32") (pintype "bidirectional"))
    )
    (net (code "7") (name "/1HA") (class "Default")
      (node (ref "IC7") (pin "2") (pinfunction "IN3_2") (pintype "bidirectional"))
      (node (ref "IC7") (pin "8") (pinfunction "IN1_8") (pintype "bidirectional"))
      (node (ref "R41") (pin "3") (pinfunction "1_3") (pintype "passive"))
    )
    (net (code "8") (name "/1HB") (class "Default")
      (node (ref "IC7") (pin "13") (pinfunction "IN4_13") (pintype "bidirectional"))
      (node (ref "IC7") (pin "7") (pinfunction "IN2_7") (pintype "bidirectional"))
      (node (ref "R41") (pin "4") (pinfunction "1_4") (pintype "passive"))
    )
    (net (code "9") (name "/1SENSE") (class "Default")
      (node (ref "R10") (pin "1") (pinfunction "1_1") (pintype "passive"))
      (node (ref "R7") (pin "1") (pinfunction "1_1") (pintype "passive"))
      (node (ref "U3") (pin "24") (pinfunction "PC1(ADC1)_24") (pintype "bidirectional"))
      (node (ref "ZD3") (pin "C") (pinfunction "C_C") (pintype "passive"))
    )
    (net (code "10") (name "/1STAT") (class "Default")
      (node (ref "IC7") (pin "4") (pinfunction "STAT3_4") (pintype "bidirectional"))
      (node (ref "U3") (pin "1") (pinfunction "PD3(INT1)_1") (pintype "bidirectional"))
    )
    (net (code "11") (name "/2HA") (class "Default")
      (node (ref "IC5") (pin "2") (pinfunction "IN3_2") (pintype "bidirectional"))
      (node (ref "IC5") (pin "8") (pinfunction "IN1_8") (pintype "bidirectional"))
      (node (ref "R41") (pin "5") (pinfunction "1_5") (pintype "passive"))
    )
    (net (code "12") (name "/2HB") (class "Default")
      (node (ref "IC5") (pin "13") (pinfunction "IN4_13") (pintype "bidirectional"))
      (node (ref "IC5") (pin "7") (pinfunction "IN2_7") (pintype "bidirectional"))
      (node (ref "R41") (pin "6") (pinfunction "1_6") (pintype "passive"))
    )
    (net (code "13") (name "/2SENSE") (class "Default")
      (node (ref "R5") (pin "1") (pinfunction "1_1") (pintype "passive"))
      (node (ref "R6") (pin "1") (pinfunction "1_1") (pintype "passive"))
      (node (ref "U3") (pin "25") (pinfunction "PC2(ADC2)_25") (pintype "bidirectional"))
      (node (ref "ZD1") (pin "C") (pinfunction "C_C") (pintype "passive"))
    )
    (net (code "14") (name "/2STAT") (class "Default")
      (node (ref "IC5") (pin "4") (pinfunction "STAT3_4") (pintype "bidirectional"))
      (node (ref "U3") (pin "2") (pinfunction "PD4(XCK/T0)_2") (pintype "bidirectional"))
    )
    (net (code "15") (name "/3HA") (class "Default")
      (node (ref "IC9") (pin "2") (pinfunction "IN3_2") (pintype "bidirectional"))
      (node (ref "IC9") (pin "8") (pinfunction "IN1_8") (pintype "bidirectional"))
      (node (ref "R41") (pin "7") (pinfunction "1_7") (pintype "passive"))
    )
    (net (code "16") (name "/3HB") (class "Default")
      (node (ref "IC9") (pin "13") (pinfunction "IN4_13") (pintype "bidirectional"))
      (node (ref "IC9") (pin "7") (pinfunction "IN2_7") (pintype "bidirectional"))
      (node (ref "R41") (pin "8") (pinfunction "1_8") (pintype "passive"))
    )
    (net (code "17") (name "/3SENSE") (class "Default")
      (node (ref "R36") (pin "1") (pinfunction "1_1") (pintype "passive"))
      (node (ref "R37") (pin "1") (pinfunction "1_1") (pintype "passive"))
      (node (ref "U3") (pin "26") (pinfunction "PC3(ADC3)_26") (pintype "bidirectional"))
      (node (ref "ZD5") (pin "C") (pinfunction "C_C") (pintype "passive"))
    )
    (net (code "18") (name "/3STAT") (class "Default")
      (node (ref "IC9") (pin "4") (pinfunction "STAT3_4") (pintype "bidirectional"))
      (node (ref "U3") (pin "9") (pinfunction "PD5(T1)_9") (pintype "bidirectional"))
    )
    (net (code "19") (name "/4HA") (class "Default")
      (node (ref "IC8") (pin "2") (pinfunction "IN3_2") (pintype "bidirectional"))
      (node (ref "IC8") (pin "8") (pinfunction "IN1_8") (pintype "bidirectional"))
      (node (ref "R57") (pin "3") (pinfunction "1_3") (pintype "passive"))
    )
    (net (code "20") (name "/4HB") (class "Default")
      (node (ref "IC8") (pin "13") (pinfunction "IN4_13") (pintype "bidirectional"))
      (node (ref "IC8") (pin "7") (pinfunction "IN2_7") (pintype "bidirectional"))
      (node (ref "R57") (pin "1") (pinfunction "1_1") (pintype "passive"))
    )
    (net (code "21") (name "/4SENSE") (class "Default")
      (node (ref "R26") (pin "1") (pinfunction "1_1") (pintype "passive"))
      (node (ref "R31") (pin "1") (pinfunction "1_1") (pintype "passive"))
      (node (ref "U3") (pin "27") (pinfunction "PC4(ADC4/SDA)_27") (pintype "bidirectional"))
      (node (ref "ZD4") (pin "C") (pinfunction "C_C") (pintype "passive"))
    )
    (net (code "22") (name "/4STAT") (class "Default")
      (node (ref "IC8") (pin "4") (pinfunction "STAT3_4") (pintype "bidirectional"))
      (node (ref "U3") (pin "10") (pinfunction "PD6(AIN0)_10") (pintype "bidirectional"))
    )
    (net (code "23") (name "/D1+") (class "Default")
      (node (ref "C32") (pin "1") (pinfunction "1_1") (pintype "passive"))
      (node (ref "IC10") (pin "12") (pinfunction "D1+_12") (pintype "bidirectional"))
      (node (ref "R29") (pin "1") (pinfunction "1_1") (pintype "passive"))
    )
    (net (code "24") (name "/D1-") (class "Default")
      (node (ref "C33") (pin "1") (pinfunction "1_1") (pintype "passive"))
      (node (ref "IC10") (pin "11") (pinfunction "D1-_11") (pintype "bidirectional"))
      (node (ref "R28") (pin "1") (pinfunction "1_1") (pintype "passive"))
    )
    (net (code "25") (name "/ISP-MISO") (class "Default")
      (node (ref "ISP1") (pin "1") (pinfunction "MISO_1") (pintype "input"))
      (node (ref "R4") (pin "2") (pinfunction "2_2") (pintype "passive"))
      (node (ref "U3") (pin "16") (pinfunction "PB4(MISO)_16") (pintype "bidirectional"))
    )
    (net (code "26") (name "/ISP-MOSI") (class "Default")
      (node (ref "ISP1") (pin "4") (pinfunction "MOSI_4") (pintype "output"))
      (node (ref "R3") (pin "2") (pinfunction "2_2") (pintype "passive"))
      (node (ref "U3") (pin "15") (pinfunction "PB3(MOSI/OC2)_15") (pintype "bidirectional"))
    )
    (net (code "27") (name "/ISP-SCK") (class "Default")
      (node (ref "ISP1") (pin "3") (pinfunction "SCK_3") (pintype "output"))
      (node (ref "R2") (pin "2") (pinfunction "2_2") (pintype "passive"))
      (node (ref "U3") (pin "17") (pinfunction "PB5(SCK)_17") (pintype "bidirectional"))
    )
    (net (code "28") (name "/LATCH") (class "Default")
      (node (ref "IC2") (pin "12") (pinfunction "RCK_12") (pintype "input"))
      (node (ref "IC3") (pin "12") (pinfunction "RCK_12") (pintype "input"))
      (node (ref "U3") (pin "14") (pinfunction "PB2(SS/OC1B)_14") (pintype "bidirectional"))
    )
    (net (code "29") (name "/MISO") (class "Default")
      (node (ref "ISP2") (pin "1") (pinfunction "MISO_1") (pintype "input"))
      (node (ref "ISP3") (pin "1") (pinfunction "MISO_1") (pintype "input"))
      (node (ref "ISP4") (pin "1") (pinfunction "MISO_1") (pintype "input"))
      (node (ref "ISP5") (pin "1") (pinfunction "MISO_1") (pintype "input"))
      (node (ref "R4") (pin "1") (pinfunction "1_1") (pintype "passive"))
    )
    (net (code "30") (name "/MOSI") (class "Default")
      (node (ref "IC2") (pin "14") (pinfunction "SER_14") (pintype "input"))
      (node (ref "ISP2") (pin "4") (pinfunction "MOSI_4") (pintype "output"))
      (node (ref "ISP3") (pin "4") (pinfunction "MOSI_4") (pintype "output"))
      (node (ref "ISP4") (pin "4") (pinfunction "MOSI_4") (pintype "output"))
      (node (ref "ISP5") (pin "4") (pinfunction "MOSI_4") (pintype "output"))
      (node (ref "R3") (pin "1") (pinfunction "1_1") (pintype "passive"))
    )
    (net (code "31") (name "/RXD") (class "Default")
      (node (ref "IC4") (pin "1") (pinfunction "TXD_1") (pintype "output"))
      (node (ref "U3") (pin "30") (pinfunction "PD0(RXD)_30") (pintype "bidirectional"))
    )
    (net (code "32") (name "/SCK") (class "Default")
      (node (ref "IC2") (pin "11") (pinfunction "SCK_11") (pintype "input"))
      (node (ref "IC3") (pin "11") (pinfunction "SCK_11") (pintype "input"))
      (node (ref "ISP2") (pin "3") (pinfunction "SCK_3") (pintype "output"))
      (node (ref "ISP3") (pin "3") (pinfunction "SCK_3") (pintype "output"))
      (node (ref "ISP4") (pin "3") (pinfunction "SCK_3") (pintype "output"))
      (node (ref "ISP5") (pin "3") (pinfunction "SCK_3") (pintype "output"))
      (node (ref "R2") (pin "1") (pinfunction "1_1") (pintype "passive"))
    )
    (net (code "33") (name "/SW0") (class "Default")
      (node (ref "Q3") (pin "1") (pinfunction "G_1") (pintype "bidirectional"))
      (node (ref "R57") (pin "2") (pinfunction "1_2") (pintype "passive"))
    )
    (net (code "34") (name "/SW1") (class "Default")
      (node (ref "Q2") (pin "1") (pinfunction "G_1") (pintype "bidirectional"))
      (node (ref "R57") (pin "4") (pinfunction "1_4") (pintype "passive"))
    )
    (net (code "35") (name "/SW2") (class "Default")
      (node (ref "Q1") (pin "1") (pinfunction "G_1") (pintype "bidirectional"))
      (node (ref "R57") (pin "5") (pinfunction "1_5") (pintype "passive"))
    )
    (net (code "36") (name "/SW3") (class "Default")
      (node (ref "JP12") (pin "1") (pinfunction "1_1") (pintype "passive"))
      (node (ref "R57") (pin "6") (pinfunction "1_6") (pintype "passive"))
    )
    (net (code "37") (name "/SW4") (class "Default")
      (node (ref "JP12") (pin "2") (pinfunction "2_2") (pintype "passive"))
      (node (ref "R57") (pin "7") (pinfunction "1_7") (pintype "passive"))
    )
    (net (code "38") (name "/SW5") (class "Default")
      (node (ref "JP12") (pin "3") (pinfunction "3_3") (pintype "passive"))
      (node (ref "R57") (pin "8") (pinfunction "1_8") (pintype "passive"))
    )
    (net (code "39") (name "/TEMP0") (class "Default")
      (node (ref "C50") (pin "1") (pinfunction "1_1") (pintype "passive"))
      (node (ref "IC12") (pin "2") (pinfunction "VO_2") (pintype "input"))
      (node (ref "U3") (pin "28") (pinfunction "PC5(ADC5/SCL)_28") (pintype "bidirectional"))
    )
    (net (code "40") (name "/TEMP1") (class "Default")
      (node (ref "C51") (pin "1") (pinfunction "1_1") (pintype "passive"))
      (node (ref "IC13") (pin "2") (pinfunction "VO_2") (pintype "input"))
      (node (ref "U3") (pin "19") (pinfunction "ADC6_19") (pintype "bidirectional"))
    )
    (net (code "41") (name "/TXD") (class "Default")
      (node (ref "IC4") (pin "4") (pinfunction "RXD_4") (pintype "input"))
      (node (ref "U3") (pin "31") (pinfunction "PD1(TXD)_31") (pintype "bidirectional"))
    )
    (net (code "42") (name "/~{EN1}") (class "Default")
      (node (ref "R39") (pin "2") (pinfunction "2_2") (pintype "passive"))
      (node (ref "U3") (pin "22") (pinfunction "ADC7_22") (pintype "bidirectional"))
    )
    (net (code "43") (name "/~{EN2}") (class "Default")
      (node (ref "R38") (pin "2") (pinfunction "2_2") (pintype "passive"))
      (node (ref "U3") (pin "11") (pinfunction "PD7(AIN1)_11") (pintype "bidirectional"))
    )
    (net (code "44") (name "/~{EN3}") (class "Default")
      (node (ref "R33") (pin "2") (pinfunction "2_2") (pintype "passive"))
      (node (ref "U3") (pin "12") (pinfunction "PB0(ICP)_12") (pintype "bidirectional"))
    )
    (net (code "45") (name "/~{EN4}") (class "Default")
      (node (ref "R32") (pin "2") (pinfunction "2_2") (pintype "passive"))
      (node (ref "U3") (pin "13") (pinfunction "PB1(OC1A)_13") (pintype "bidirectional"))
    )
    (net (code "46") (name "/~{RST}") (class "Default")
      (node (ref "C43") (pin "1") (pinfunction "1_1") (pintype "passive"))
      (node (ref "ISP1") (pin "5") (pinfunction "RST_5") (pintype "output"))
      (node (ref "R1") (pin "1") (pinfunction "1_1") (pintype "passive"))
      (node (ref "SW1") (pin "B") (pinfunction "S_B") (pintype "passive"))
      (node (ref "U3") (pin "29") (pinfunction "PC6(/RESET)_29") (pintype "bidirectional"))
    )
    (net (code "47") (name "3.3V") (class "Default")
      (node (ref "C35") (pin "1") (pinfunction "1_1") (pintype "passive"))
      (node (ref "C36") (pin "1") (pinfunction "1_1") (pintype "passive"))
      (node (ref "IC10") (pin "10") (pinfunction "~{OVRCUR1}_10") (pintype "bidirectional"))
      (node (ref "IC10") (pin "14") (pinfunction "~{OVRCUR2}_14") (pintype "bidirectional"))
      (node (ref "IC10") (pin "18") (pinfunction "~{OVRCUR3}_18") (pintype "bidirectional"))
      (node (ref "IC10") (pin "22") (pinfunction "~{OVRCUR4}_22") (pintype "bidirectional"))
      (node (ref "IC10") (pin "25") (pinfunction "VCC_25") (pintype "bidirectional"))
      (node (ref "IC10") (pin "26") (pinfunction "~{EXTMEM}_26") (pintype "bidirectional"))
      (node (ref "IC10") (pin "3") (pinfunction "VCC_3") (pintype "bidirectional"))
      (node (ref "IC10") (pin "4") (pinfunction "~{RST}_4") (pintype "bidirectional"))
      (node (ref "R11") (pin "2") (pinfunction "2_2") (pintype "passive"))
      (node (ref "U2") (pin "5") (pinfunction "OUT_5") (pintype "passive"))
    )
    (net (code "48") (name "AGND") (class "Default")
      (node (ref "C44") (pin "2") (pinfunction "2_2") (pintype "passive"))
      (node (ref "C46") (pin "2") (pinfunction "2_2") (pintype "passive"))
      (node (ref "C47") (pin "2") (pinfunction "2_2") (pintype "passive"))
      (node (ref "C48") (pin "2") (pinfunction "2_2") (pintype "passive"))
      (node (ref "C49") (pin "2") (pinfunction "2_2") (pintype "passive"))
      (node (ref "C50") (pin "2") (pinfunction "2_2") (pintype "passive"))
      (node (ref "C51") (pin "2") (pinfunction "2_2") (pintype "passive"))
      (node (ref "IC12") (pin "3") (pinfunction "GND_3") (pintype "power_in"))
      (node (ref "IC13") (pin "3") (pinfunction "GND_3") (pintype "power_in"))
      (node (ref "R10") (pin "2") (pinfunction "2_2") (pintype "passive"))
      (node (ref "R31") (pin "2") (pinfunction "2_2") (pintype "passive"))
      (node (ref "R35") (pin "1") (pinfunction "1_1") (pintype "passive"))
      (node (ref "R37") (pin "2") (pinfunction "2_2") (pintype "passive"))
      (node (ref "R5") (pin "2") (pinfunction "2_2") (pintype "passive"))
      (node (ref "R8") (pin "2") (pinfunction "2_2") (pintype "passive"))
      (node (ref "U3") (pin "5") (pinfunction "AGND_5") (pintype "bidirectional"))
      (node (ref "ZD1") (pin "A") (pinfunction "A_A") (pintype "passive"))
      (node (ref "ZD2") (pin "A") (pinfunction "A_A") (pintype "passive"))
      (node (ref "ZD3") (pin "A") (pinfunction "A_A") (pintype "passive"))
      (node (ref "ZD4") (pin "A") (pinfunction "A_A") (pintype "passive"))
      (node (ref "ZD5") (pin "A") (pinfunction "A_A") (pintype "passive"))
    )
    (net (code "49") (name "GND") (class "Default")
      (node (ref "C1") (pin "-") (pinfunction "-_-") (pintype "passive"))
      (node (ref "C10") (pin "-") (pinfunction "-_-") (pintype "passive"))
      (node (ref "C11") (pin "2") (pinfunction "2_2") (pintype "passive"))
      (node (ref "C13") (pin "2") (pinfunction "2_2") (pintype "passive"))
      (node (ref "C14") (pin "-") (pinfunction "-_-") (pintype "passive"))
      (node (ref "C15") (pin "2") (pinfunction "2_2") (pintype "passive"))
      (node (ref "C17") (pin "2") (pinfunction "2_2") (pintype "passive"))
      (node (ref "C18") (pin "-") (pinfunction "-_-") (pintype "passive"))
      (node (ref "C19") (pin "2") (pinfunction "2_2") (pintype "passive"))
      (node (ref "C2") (pin "-") (pinfunction "-_-") (pintype "passive"))
      (node (ref "C21") (pin "2") (pinfunction "2_2") (pintype "passive"))
      (node (ref "C22") (pin "2") (pinfunction "2_2") (pintype "passive"))
      (node (ref "C23") (pin "2") (pinfunction "2_2") (pintype "passive"))
      (node (ref "C24") (pin "2") (pinfunction "2_2") (pintype "passive"))
      (node (ref "C25") (pin "2") (pinfunction "2_2") (pintype "passive"))
      (node (ref "C26") (pin "2") (pinfunction "2_2") (pintype "passive"))
      (node (ref "C27") (pin "2") (pinfunction "2_2") (pintype "passive"))
      (node (ref "C28") (pin "2") (pinfunction "2_2") (pintype "passive"))
      (node (ref "C29") (pin "2") (pinfunction "2_2") (pintype "passive"))
      (node (ref "C3") (pin "2") (pinfunction "2_2") (pintype "passive"))
      (node (ref "C30") (pin "2") (pinfunction "2_2") (pintype "passive"))
      (node (ref "C31") (pin "2") (pinfunction "2_2") (pintype "passive"))
      (node (ref "C32") (pin "2") (pinfunction "2_2") (pintype "passive"))
      (node (ref "C33") (pin "2") (pinfunction "2_2") (pintype "passive"))
      (node (ref "C34") (pin "2") (pinfunction "2_2") (pintype "passive"))
      (node (ref "C35") (pin "2") (pinfunction "2_2") (pintype "passive"))
      (node (ref "C36") (pin "2") (pinfunction "2_2") (pintype "passive"))
      (node (ref "C37") (pin "2") (pinfunction "2_2") (pintype "passive"))
      (node (ref "C38") (pin "2") (pinfunction "2_2") (pintype "passive"))
      (node (ref "C39") (pin "-") (pinfunction "-_-") (pintype "passive"))
      (node (ref "C4") (pin "-") (pinfunction "-_-") (pintype "passive"))
      (node (ref "C40") (pin "2") (pinfunction "2_2") (pintype "passive"))
      (node (ref "C42") (pin "2") (pinfunction "2_2") (pintype "passive"))
      (node (ref "C5") (pin "2") (pinfunction "2_2") (pintype "passive"))
      (node (ref "C52") (pin "2") (pinfunction "2_2") (pintype "passive"))
      (node (ref "C53") (pin "-") (pinfunction "-_-") (pintype "passive"))
      (node (ref "C54") (pin "-") (pinfunction "-_-") (pintype "passive"))
      (node (ref "C55") (pin "-") (pinfunction "-_-") (pintype "passive"))
      (node (ref "C7") (pin "2") (pinfunction "2_2") (pintype "passive"))
      (node (ref "C8") (pin "2") (pinfunction "2_2") (pintype "passive"))
      (node (ref "C9") (pin "2") (pinfunction "2_2") (pintype "passive"))
      (node (ref "D1") (pin "A") (pinfunction "A_A") (pintype "passive"))
      (node (ref "D11") (pin "A") (pinfunction "A_A") (pintype "passive"))
      (node (ref "D13") (pin "A") (pinfunction "A_A") (pintype "passive"))
      (node (ref "D15") (pin "A") (pinfunction "A_A") (pintype "passive"))
      (node (ref "D17") (pin "A") (pinfunction "A_A") (pintype "passive"))
      (node (ref "D19") (pin "A") (pinfunction "A_A") (pintype "passive"))
      (node (ref "D21") (pin "A") (pinfunction "A_A") (pintype "passive"))
      (node (ref "D3") (pin "A") (pinfunction "A_A") (pintype "passive"))
      (node (ref "D5") (pin "A") (pinfunction "A_A") (pintype "passive"))
      (node (ref "D7") (pin "A") (pinfunction "A_A") (pintype "passive"))
      (node (ref "D9") (pin "A") (pinfunction "A_A") (pintype "passive"))
      (node (ref "IC1") (pin "3") (pinfunction "GND_3") (pintype "power_in"))
      (node (ref "IC1") (pin "5") (pinfunction "EN_5") (pintype "input"))
      (node (ref "IC1") (pin "6") (pinfunction "GND_6") (pintype "power_in"))
      (node (ref "IC10") (pin "27") (pinfunction "PLL/48M_27") (pintype "bidirectional"))
      (node (ref "IC10") (pin "28") (pinfunction "GND_28") (pintype "bidirectional"))
      (node (ref "IC10") (pin "31") (pinfunction "TSTMODE_31") (pintype "bidirectional"))
      (node (ref "IC10") (pin "6") (pinfunction "EEDATA/GANGED_6") (pintype "bidirectional"))
      (node (ref "IC10") (pin "7") (pinfunction "GND_7") (pintype "bidirectional"))
      (node (ref "IC10") (pin "8") (pinfunction "BUSPWR_8") (pintype "bidirectional"))
      (node (ref "IC2") (pin "13") (pinfunction "G_13") (pintype "input"))
      (node (ref "IC2") (pin "8") (pinfunction "GND_8") (pintype "power_in"))
      (node (ref "IC3") (pin "13") (pinfunction "G_13") (pintype "input"))
      (node (ref "IC3") (pin "8") (pinfunction "GND_8") (pintype "power_in"))
      (node (ref "IC4") (pin "13") (pinfunction "GND_13") (pintype "power_in"))
      (node (ref "IC4") (pin "5") (pinfunction "GND_5") (pintype "power_in"))
      (node (ref "IC5") (pin "16") (pinfunction "SOURCE4_16") (pintype "bidirectional"))
      (node (ref "IC5") (pin "17") (pinfunction "SOURCE4_17") (pintype "bidirectional"))
      (node (ref "IC5") (pin "26") (pinfunction "SOURCE3_26") (pintype "bidirectional"))
      (node (ref "IC5") (pin "27") (pinfunction "SOURCE3_27") (pintype "bidirectional"))
      (node (ref "IC5") (pin "6") (pinfunction "GND_6") (pintype "bidirectional"))
      (node (ref "IC6") (pin "16") (pinfunction "SOURCE4_16") (pintype "bidirectional"))
      (node (ref "IC6") (pin "17") (pinfunction "SOURCE4_17") (pintype "bidirectional"))
      (node (ref "IC6") (pin "26") (pinfunction "SOURCE3_26") (pintype "bidirectional"))
      (node (ref "IC6") (pin "27") (pinfunction "SOURCE3_27") (pintype "bidirectional"))
      (node (ref "IC6") (pin "6") (pinfunction "GND_6") (pintype "bidirectional"))
      (node (ref "IC7") (pin "16") (pinfunction "SOURCE4_16") (pintype "bidirectional"))
      (node (ref "IC7") (pin "17") (pinfunction "SOURCE4_17") (pintype "bidirectional"))
      (node (ref "IC7") (pin "26") (pinfunction "SOURCE3_26") (pintype "bidirectional"))
      (node (ref "IC7") (pin "27") (pinfunction "SOURCE3_27") (pintype "bidirectional"))
      (node (ref "IC7") (pin "6") (pinfunction "GND_6") (pintype "bidirectional"))
      (node (ref "IC8") (pin "16") (pinfunction "SOURCE4_16") (pintype "bidirectional"))
      (node (ref "IC8") (pin "17") (pinfunction "SOURCE4_17") (pintype "bidirectional"))
      (node (ref "IC8") (pin "26") (pinfunction "SOURCE3_26") (pintype "bidirectional"))
      (node (ref "IC8") (pin "27") (pinfunction "SOURCE3_27") (pintype "bidirectional"))
      (node (ref "IC8") (pin "6") (pinfunction "GND_6") (pintype "bidirectional"))
      (node (ref "IC9") (pin "16") (pinfunction "SOURCE4_16") (pintype "bidirectional"))
      (node (ref "IC9") (pin "17") (pinfunction "SOURCE4_17") (pintype "bidirectional"))
      (node (ref "IC9") (pin "26") (pinfunction "SOURCE3_26") (pintype "bidirectional"))
      (node (ref "IC9") (pin "27") (pinfunction "SOURCE3_27") (pintype "bidirectional"))
      (node (ref "IC9") (pin "6") (pinfunction "GND_6") (pintype "bidirectional"))
      (node (ref "ISP1") (pin "6") (pinfunction "GND_6") (pintype "power_in"))
      (node (ref "ISP2") (pin "6") (pinfunction "GND_6") (pintype "power_in"))
      (node (ref "ISP3") (pin "6") (pinfunction "GND_6") (pintype "power_in"))
      (node (ref "ISP4") (pin "6") (pinfunction "GND_6") (pintype "power_in"))
      (node (ref "ISP5") (pin "6") (pinfunction "GND_6") (pintype "power_in"))
      (node (ref "JP1") (pin "1") (pinfunction "1_1") (pintype "passive"))
      (node (ref "JP11") (pin "1") (pinfunction "1_1") (pintype "passive"))
      (node (ref "JP13") (pin "1") (pinfunction "1_1") (pintype "passive"))
      (node (ref "JP17") (pin "1") (pinfunction "1_1") (pintype "passive"))
      (node (ref "Q1") (pin "2") (pinfunction "S_2") (pintype "bidirectional"))
      (node (ref "Q2") (pin "2") (pinfunction "S_2") (pintype "bidirectional"))
      (node (ref "Q3") (pin "2") (pinfunction "S_2") (pintype "bidirectional"))
      (node (ref "R14") (pin "2") (pinfunction "2_2") (pintype "passive"))
      (node (ref "R15") (pin "2") (pinfunction "2_2") (pintype "passive"))
      (node (ref "R22") (pin "2") (pinfunction "2_2") (pintype "passive"))
      (node (ref "R23") (pin "2") (pinfunction "2_2") (pintype "passive"))
      (node (ref "R24") (pin "2") (pinfunction "2_2") (pintype "passive"))
      (node (ref "R25") (pin "2") (pinfunction "2_2") (pintype "passive"))
      (node (ref "R27") (pin "1") (pinfunction "1_1") (pintype "passive"))
      (node (ref "R30") (pin "1") (pinfunction "1_1") (pintype "passive"))
      (node (ref "R34") (pin "2") (pinfunction "2_2") (pintype "passive"))
      (node (ref "R35") (pin "2") (pinfunction "2_2") (pintype "passive"))
      (node (ref "SW1") (pin "A") (pinfunction "P_A") (pintype "passive"))
      (node (ref "U$6") (pin "A") (pinfunction "1_A") (pintype "passive"))
      (node (ref "U$7") (pin "A") (pinfunction "1_A") (pintype "passive"))
      (node (ref "U$8") (pin "A") (pinfunction "1_A") (pintype "passive"))
      (node (ref "U2") (pin "2") (pinfunction "GND_2") (pintype "input"))
      (node (ref "U3") (pin "21") (pinfunction "GND_21") (pintype "bidirectional"))
      (node (ref "U3") (pin "3") (pinfunction "GND_3") (pintype "bidirectional"))
      (node (ref "Y1") (pin "2") (pinfunction "2_2") (pintype "passive"))
      (node (ref "Y2") (pin "2") (pinfunction "2_2") (pintype "passive"))
    )
    (net (code "50") (name "Net-(C6-Pad1)") (class "Default")
      (node (ref "C6") (pin "1") (pinfunction "1_1") (pintype "passive"))
      (node (ref "D2") (pin "A") (pinfunction "A_A") (pintype "passive"))
      (node (ref "D3") (pin "C") (pinfunction "C_C") (pintype "passive"))
      (node (ref "IC5") (pin "1") (pinfunction "DRAIN3_1") (pintype "bidirectional"))
      (node (ref "IC5") (pin "22") (pinfunction "SOURCE2_22") (pintype "bidirectional"))
      (node (ref "IC5") (pin "23") (pinfunction "SOURCE2_23") (pintype "bidirectional"))
      (node (ref "IC5") (pin "25") (pinfunction "DRAIN3_25") (pintype "bidirectional"))
      (node (ref "IC5") (pin "28") (pinfunction "DRAIN3_28") (pintype "bidirectional"))
      (node (ref "IC5") (pin "3") (pinfunction "DRAIN3_3") (pintype "bidirectional"))
      (node (ref "JP2") (pin "2") (pinfunction "2_2") (pintype "passive"))
    )
    (net (code "51") (name "Net-(C6-Pad2)") (class "Default")
      (node (ref "C6") (pin "2") (pinfunction "2_2") (pintype "passive"))
      (node (ref "D4") (pin "A") (pinfunction "A_A") (pintype "passive"))
      (node (ref "D5") (pin "C") (pinfunction "C_C") (pintype "passive"))
      (node (ref "IC5") (pin "12") (pinfunction "DRAIN4_12") (pintype "bidirectional"))
      (node (ref "IC5") (pin "14") (pinfunction "DRAIN4_14") (pintype "bidirectional"))
      (node (ref "IC5") (pin "15") (pinfunction "DRAIN4_15") (pintype "bidirectional"))
      (node (ref "IC5") (pin "18") (pinfunction "DRAIN4_18") (pintype "bidirectional"))
      (node (ref "IC5") (pin "20") (pinfunction "SOURCE1_20") (pintype "bidirectional"))
      (node (ref "IC5") (pin "21") (pinfunction "SOURCE1_21") (pintype "bidirectional"))
      (node (ref "JP2") (pin "1") (pinfunction "1_1") (pintype "passive"))
    )
    (net (code "52") (name "Net-(C12-Pad1)") (class "Default")
      (node (ref "C12") (pin "1") (pinfunction "1_1") (pintype "passive"))
      (node (ref "D6") (pin "A") (pinfunction "A_A") (pintype "passive"))
      (node (ref "D7") (pin "C") (pinfunction "C_C") (pintype "passive"))
      (node (ref "IC6") (pin "1") (pinfunction "DRAIN3_1") (pintype "bidirectional"))
      (node (ref "IC6") (pin "22") (pinfunction "SOURCE2_22") (pintype "bidirectional"))
      (node (ref "IC6") (pin "23") (pinfunction "SOURCE2_23") (pintype "bidirectional"))
      (node (ref "IC6") (pin "25") (pinfunction "DRAIN3_25") (pintype "bidirectional"))
      (node (ref "IC6") (pin "28") (pinfunction "DRAIN3_28") (pintype "bidirectional"))
      (node (ref "IC6") (pin "3") (pinfunction "DRAIN3_3") (pintype "bidirectional"))
      (node (ref "JP3") (pin "2") (pinfunction "2_2") (pintype "passive"))
    )
    (net (code "53") (name "Net-(C12-Pad2)") (class "Default")
      (node (ref "C12") (pin "2") (pinfunction "2_2") (pintype "passive"))
      (node (ref "D8") (pin "A") (pinfunction "A_A") (pintype "passive"))
      (node (ref "D9") (pin "C") (pinfunction "C_C") (pintype "passive"))
      (node (ref "IC6") (pin "12") (pinfunction "DRAIN4_12") (pintype "bidirectional"))
      (node (ref "IC6") (pin "14") (pinfunction "DRAIN4_14") (pintype "bidirectional"))
      (node (ref "IC6") (pin "15") (pinfunction "DRAIN4_15") (pintype "bidirectional"))
      (node (ref "IC6") (pin "18") (pinfunction "DRAIN4_18") (pintype "bidirectional"))
      (node (ref "IC6") (pin "20") (pinfunction "SOURCE1_20") (pintype "bidirectional"))
      (node (ref "IC6") (pin "21") (pinfunction "SOURCE1_21") (pintype "bidirectional"))
      (node (ref "JP3") (pin "1") (pinfunction "1_1") (pintype "passive"))
    )
    (net (code "54") (name "Net-(C16-Pad1)") (class "Default")
      (node (ref "C16") (pin "1") (pinfunction "1_1") (pintype "passive"))
      (node (ref "D10") (pin "A") (pinfunction "A_A") (pintype "passive"))
      (node (ref "D11") (pin "C") (pinfunction "C_C") (pintype "passive"))
      (node (ref "IC7") (pin "1") (pinfunction "DRAIN3_1") (pintype "bidirectional"))
      (node (ref "IC7") (pin "22") (pinfunction "SOURCE2_22") (pintype "bidirectional"))
      (node (ref "IC7") (pin "23") (pinfunction "SOURCE2_23") (pintype "bidirectional"))
      (node (ref "IC7") (pin "25") (pinfunction "DRAIN3_25") (pintype "bidirectional"))
      (node (ref "IC7") (pin "28") (pinfunction "DRAIN3_28") (pintype "bidirectional"))
      (node (ref "IC7") (pin "3") (pinfunction "DRAIN3_3") (pintype "bidirectional"))
      (node (ref "JP4") (pin "2") (pinfunction "2_2") (pintype "passive"))
    )
    (net (code "55") (name "Net-(C16-Pad2)") (class "Default")
      (node (ref "C16") (pin "2") (pinfunction "2_2") (pintype "passive"))
      (node (ref "D12") (pin "A") (pinfunction "A_A") (pintype "passive"))
      (node (ref "D13") (pin "C") (pinfunction "C_C") (pintype "passive"))
      (node (ref "IC7") (pin "12") (pinfunction "DRAIN4_12") (pintype "bidirectional"))
      (node (ref "IC7") (pin "14") (pinfunction "DRAIN4_14") (pintype "bidirectional"))
      (node (ref "IC7") (pin "15") (pinfunction "DRAIN4_15") (pintype "bidirectional"))
      (node (ref "IC7") (pin "18") (pinfunction "DRAIN4_18") (pintype "bidirectional"))
      (node (ref "IC7") (pin "20") (pinfunction "SOURCE1_20") (pintype "bidirectional"))
      (node (ref "IC7") (pin "21") (pinfunction "SOURCE1_21") (pintype "bidirectional"))
      (node (ref "JP4") (pin "1") (pinfunction "1_1") (pintype "passive"))
    )
    (net (code "56") (name "Net-(C20-Pad1)") (class "Default")
      (node (ref "C20") (pin "1") (pinfunction "1_1") (pintype "passive"))
      (node (ref "D14") (pin "A") (pinfunction "A_A") (pintype "passive"))
      (node (ref "D15") (pin "C") (pinfunction "C_C") (pintype "passive"))
      (node (ref "IC8") (pin "1") (pinfunction "DRAIN3_1") (pintype "bidirectional"))
      (node (ref "IC8") (pin "22") (pinfunction "SOURCE2_22") (pintype "bidirectional"))
      (node (ref "IC8") (pin "23") (pinfunction "SOURCE2_23") (pintype "bidirectional"))
      (node (ref "IC8") (pin "25") (pinfunction "DRAIN3_25") (pintype "bidirectional"))
      (node (ref "IC8") (pin "28") (pinfunction "DRAIN3_28") (pintype "bidirectional"))
      (node (ref "IC8") (pin "3") (pinfunction "DRAIN3_3") (pintype "bidirectional"))
      (node (ref "JP5") (pin "2") (pinfunction "2_2") (pintype "passive"))
    )
    (net (code "57") (name "Net-(C20-Pad2)") (class "Default")
      (node (ref "C20") (pin "2") (pinfunction "2_2") (pintype "passive"))
      (node (ref "D16") (pin "A") (pinfunction "A_A") (pintype "passive"))
      (node (ref "D17") (pin "C") (pinfunction "C_C") (pintype "passive"))
      (node (ref "IC8") (pin "12") (pinfunction "DRAIN4_12") (pintype "bidirectional"))
      (node (ref "IC8") (pin "14") (pinfunction "DRAIN4_14") (pintype "bidirectional"))
      (node (ref "IC8") (pin "15") (pinfunction "DRAIN4_15") (pintype "bidirectional"))
      (node (ref "IC8") (pin "18") (pinfunction "DRAIN4_18") (pintype "bidirectional"))
      (node (ref "IC8") (pin "20") (pinfunction "SOURCE1_20") (pintype "bidirectional"))
      (node (ref "IC8") (pin "21") (pinfunction "SOURCE1_21") (pintype "bidirectional"))
      (node (ref "JP5") (pin "1") (pinfunction "1_1") (pintype "passive"))
    )
    (net (code "58") (name "Net-(C41-Pad1)") (class "Default")
      (node (ref "C41") (pin "1") (pinfunction "1_1") (pintype "passive"))
      (node (ref "D18") (pin "A") (pinfunction "A_A") (pintype "passive"))
      (node (ref "D19") (pin "C") (pinfunction "C_C") (pintype "passive"))
      (node (ref "IC9") (pin "1") (pinfunction "DRAIN3_1") (pintype "bidirectional"))
      (node (ref "IC9") (pin "22") (pinfunction "SOURCE2_22") (pintype "bidirectional"))
      (node (ref "IC9") (pin "23") (pinfunction "SOURCE2_23") (pintype "bidirectional"))
      (node (ref "IC9") (pin "25") (pinfunction "DRAIN3_25") (pintype "bidirectional"))
      (node (ref "IC9") (pin "28") (pinfunction "DRAIN3_28") (pintype "bidirectional"))
      (node (ref "IC9") (pin "3") (pinfunction "DRAIN3_3") (pintype "bidirectional"))
      (node (ref "JP6") (pin "2") (pinfunction "2_2") (pintype "passive"))
    )
    (net (code "59") (name "Net-(C41-Pad2)") (class "Default")
      (node (ref "C41") (pin "2") (pinfunction "2_2") (pintype "passive"))
      (node (ref "D20") (pin "A") (pinfunction "A_A") (pintype "passive"))
      (node (ref "D21") (pin "C") (pinfunction "C_C") (pintype "passive"))
      (node (ref "IC9") (pin "12") (pinfunction "DRAIN4_12") (pintype "bidirectional"))
      (node (ref "IC9") (pin "14") (pinfunction "DRAIN4_14") (pintype "bidirectional"))
      (node (ref "IC9") (pin "15") (pinfunction "DRAIN4_15") (pintype "bidirectional"))
      (node (ref "IC9") (pin "18") (pinfunction "DRAIN4_18") (pintype "bidirectional"))
      (node (ref "IC9") (pin "20") (pinfunction "SOURCE1_20") (pintype "bidirectional"))
      (node (ref "IC9") (pin "21") (pinfunction "SOURCE1_21") (pintype "bidirectional"))
      (node (ref "JP6") (pin "1") (pinfunction "1_1") (pintype "passive"))
    )
    (net (code "60") (name "Net-(F1-Pad2)") (class "Default")
      (node (ref "F1") (pin "2") (pinfunction "2_2") (pintype "passive"))
      (node (ref "JP17") (pin "4") (pinfunction "4_4") (pintype "passive"))
    )
    (net (code "61") (name "Net-(F2-Pad2)") (class "Default")
      (node (ref "F2") (pin "2") (pinfunction "2_2") (pintype "passive"))
      (node (ref "JP13") (pin "4") (pinfunction "4_4") (pintype "passive"))
    )
    (net (code "62") (name "Net-(F3-Pad2)") (class "Default")
      (node (ref "F3") (pin "2") (pinfunction "2_2") (pintype "passive"))
      (node (ref "JP11") (pin "4") (pinfunction "4_4") (pintype "passive"))
    )
    (net (code "63") (name "Net-(IC1-OUT)") (class "Default")
      (node (ref "D1") (pin "C") (pinfunction "C_C") (pintype "passive"))
      (node (ref "IC1") (pin "2") (pinfunction "OUT_2") (pintype "output"))
      (node (ref "L18") (pin "1") (pinfunction "1_1") (pintype "passive"))
    )
    (net (code "64") (name "Net-(IC2-QA)") (class "Default")
      (node (ref "IC2") (pin "15") (pinfunction "QA_15") (pintype "tri_state"))
      (node (ref "R41") (pin "15") (pinfunction "2_15") (pintype "passive"))
    )
    (net (code "65") (name "Net-(IC2-QB)") (class "Default")
      (node (ref "IC2") (pin "1") (pinfunction "QB_1") (pintype "tri_state"))
      (node (ref "R41") (pin "16") (pinfunction "2_16") (pintype "passive"))
    )
    (net (code "66") (name "Net-(IC2-QC)") (class "Default")
      (node (ref "IC2") (pin "2") (pinfunction "QC_2") (pintype "tri_state"))
      (node (ref "R41") (pin "14") (pinfunction "2_14") (pintype "passive"))
    )
    (net (code "67") (name "Net-(IC2-QD)") (class "Default")
      (node (ref "IC2") (pin "3") (pinfunction "QD_3") (pintype "tri_state"))
      (node (ref "R41") (pin "13") (pinfunction "2_13") (pintype "passive"))
    )
    (net (code "68") (name "Net-(IC2-QE)") (class "Default")
      (node (ref "IC2") (pin "4") (pinfunction "QE_4") (pintype "tri_state"))
      (node (ref "R41") (pin "12") (pinfunction "2_12") (pintype "passive"))
    )
    (net (code "69") (name "Net-(IC2-QF)") (class "Default")
      (node (ref "IC2") (pin "5") (pinfunction "QF_5") (pintype "tri_state"))
      (node (ref "R41") (pin "11") (pinfunction "2_11") (pintype "passive"))
    )
    (net (code "70") (name "Net-(IC2-QG)") (class "Default")
      (node (ref "IC2") (pin "6") (pinfunction "QG_6") (pintype "tri_state"))
      (node (ref "R41") (pin "10") (pinfunction "2_10") (pintype "passive"))
    )
    (net (code "71") (name "Net-(IC2-QH)") (class "Default")
      (node (ref "IC2") (pin "7") (pinfunction "QH_7") (pintype "tri_state"))
      (node (ref "R41") (pin "9") (pinfunction "2_9") (pintype "passive"))
    )
    (net (code "72") (name "Net-(IC2-QH*)") (class "Default")
      (node (ref "IC2") (pin "9") (pinfunction "QH*_9") (pintype "tri_state"))
      (node (ref "IC3") (pin "14") (pinfunction "SER_14") (pintype "input"))
    )
    (net (code "73") (name "Net-(IC3-QA)") (class "Default")
      (node (ref "IC3") (pin "15") (pinfunction "QA_15") (pintype "tri_state"))
      (node (ref "R57") (pin "14") (pinfunction "2_14") (pintype "passive"))
    )
    (net (code "74") (name "Net-(IC3-QB)") (class "Default")
      (node (ref "IC3") (pin "1") (pinfunction "QB_1") (pintype "tri_state"))
      (node (ref "R57") (pin "16") (pinfunction "2_16") (pintype "passive"))
    )
    (net (code "75") (name "Net-(IC3-QC)") (class "Default")
      (node (ref "IC3") (pin "2") (pinfunction "QC_2") (pintype "tri_state"))
      (node (ref "R57") (pin "15") (pinfunction "2_15") (pintype "passive"))
    )
    (net (code "76") (name "Net-(IC3-QD)") (class "Default")
      (node (ref "IC3") (pin "3") (pinfunction "QD_3") (pintype "tri_state"))
      (node (ref "R57") (pin "13") (pinfunction "2_13") (pintype "passive"))
    )
    (net (code "77") (name "Net-(IC3-QE)") (class "Default")
      (node (ref "IC3") (pin "4") (pinfunction "QE_4") (pintype "tri_state"))
      (node (ref "R57") (pin "12") (pinfunction "2_12") (pintype "passive"))
    )
    (net (code "78") (name "Net-(IC3-QF)") (class "Default")
      (node (ref "IC3") (pin "5") (pinfunction "QF_5") (pintype "tri_state"))
      (node (ref "R57") (pin "11") (pinfunction "2_11") (pintype "passive"))
    )
    (net (code "79") (name "Net-(IC3-QG)") (class "Default")
      (node (ref "IC3") (pin "6") (pinfunction "QG_6") (pintype "tri_state"))
      (node (ref "R57") (pin "10") (pinfunction "2_10") (pintype "passive"))
    )
    (net (code "80") (name "Net-(IC3-QH)") (class "Default")
      (node (ref "IC3") (pin "7") (pinfunction "QH_7") (pintype "tri_state"))
      (node (ref "R57") (pin "9") (pinfunction "2_9") (pintype "passive"))
    )
    (net (code "81") (name "Net-(IC4-3V3OUT)") (class "Default")
      (node (ref "C23") (pin "1") (pinfunction "1_1") (pintype "passive"))
      (node (ref "IC4") (pin "10") (pinfunction "3V3OUT_10") (pintype "power_in"))
      (node (ref "IC4") (pin "11") (pinfunction "~{RESET}_11") (pintype "bidirectional"))
      (node (ref "IC4") (pin "3") (pinfunction "VCCIO_3") (pintype "power_in"))
    )
    (net (code "82") (name "Net-(IC4-USB+)") (class "Default")
      (node (ref "IC4") (pin "8") (pinfunction "USB+_8") (pintype "output"))
      (node (ref "R29") (pin "2") (pinfunction "2_2") (pintype "passive"))
      (node (ref "R30") (pin "2") (pinfunction "2_2") (pintype "passive"))
    )
    (net (code "83") (name "Net-(IC4-USB-)") (class "Default")
      (node (ref "IC4") (pin "9") (pinfunction "USB-_9") (pintype "input"))
      (node (ref "R27") (pin "2") (pinfunction "2_2") (pintype "passive"))
      (node (ref "R28") (pin "2") (pinfunction "2_2") (pintype "passive"))
    )
    (net (code "84") (name "Net-(IC4-~{RTS})") (class "Default")
      (node (ref "C43") (pin "2") (pinfunction "2_2") (pintype "passive"))
      (node (ref "IC4") (pin "2") (pinfunction "~{RTS}_2") (pintype "bidirectional"))
    )
    (net (code "85") (name "Net-(IC5-SENSE)") (class "Default")
      (node (ref "IC5") (pin "9") (pinfunction "SENSE_9") (pintype "bidirectional"))
      (node (ref "R6") (pin "2") (pinfunction "2_2") (pintype "passive"))
    )
    (net (code "86") (name "Net-(IC6-SENSE)") (class "Default")
      (node (ref "IC6") (pin "9") (pinfunction "SENSE_9") (pintype "bidirectional"))
      (node (ref "R9") (pin "2") (pinfunction "2_2") (pintype "passive"))
    )
    (net (code "87") (name "Net-(IC7-SENSE)") (class "Default")
      (node (ref "IC7") (pin "9") (pinfunction "SENSE_9") (pintype "bidirectional"))
      (node (ref "R7") (pin "2") (pinfunction "2_2") (pintype "passive"))
    )
    (net (code "88") (name "Net-(IC8-SENSE)") (class "Default")
      (node (ref "IC8") (pin "9") (pinfunction "SENSE_9") (pintype "bidirectional"))
      (node (ref "R26") (pin "2") (pinfunction "2_2") (pintype "passive"))
    )
    (net (code "89") (name "Net-(IC9-SENSE)") (class "Default")
      (node (ref "IC9") (pin "9") (pinfunction "SENSE_9") (pintype "bidirectional"))
      (node (ref "R36") (pin "2") (pinfunction "2_2") (pintype "passive"))
    )
    (net (code "90") (name "Net-(IC10-D0+)") (class "Default")
      (node (ref "C24") (pin "1") (pinfunction "1_1") (pintype "passive"))
      (node (ref "IC10") (pin "1") (pinfunction "D0+_1") (pintype "bidirectional"))
      (node (ref "R11") (pin "1") (pinfunction "1_1") (pintype "passive"))
      (node (ref "R12") (pin "1") (pinfunction "1_1") (pintype "passive"))
      (node (ref "U$1") (pin "C") (pinfunction "2_C") (pintype "passive"))
    )
    (net (code "91") (name "Net-(IC10-D0-)") (class "Default")
      (node (ref "C9") (pin "1") (pinfunction "1_1") (pintype "passive"))
      (node (ref "IC10") (pin "2") (pinfunction "D0-_2") (pintype "bidirectional"))
      (node (ref "R13") (pin "1") (pinfunction "1_1") (pintype "passive"))
      (node (ref "U$1") (pin "A") (pinfunction "1_A") (pintype "passive"))
    )
    (net (code "92") (name "Net-(IC10-D2+)") (class "Default")
      (node (ref "C30") (pin "1") (pinfunction "1_1") (pintype "passive"))
      (node (ref "IC10") (pin "16") (pinfunction "D2+_16") (pintype "bidirectional"))
      (node (ref "R16") (pin "2") (pinfunction "2_2") (pintype "passive"))
    )
    (net (code "93") (name "Net-(IC10-D2-)") (class "Default")
      (node (ref "C29") (pin "1") (pinfunction "1_1") (pintype "passive"))
      (node (ref "IC10") (pin "15") (pinfunction "D2-_15") (pintype "bidirectional"))
      (node (ref "R17") (pin "2") (pinfunction "2_2") (pintype "passive"))
    )
    (net (code "94") (name "Net-(IC10-D3+)") (class "Default")
      (node (ref "C28") (pin "1") (pinfunction "1_1") (pintype "passive"))
      (node (ref "IC10") (pin "20") (pinfunction "D3+_20") (pintype "bidirectional"))
      (node (ref "R18") (pin "2") (pinfunction "2_2") (pintype "passive"))
    )
    (net (code "95") (name "Net-(IC10-D3-)") (class "Default")
      (node (ref "C27") (pin "1") (pinfunction "1_1") (pintype "passive"))
      (node (ref "IC10") (pin "19") (pinfunction "D3-_19") (pintype "bidirectional"))
      (node (ref "R19") (pin "2") (pinfunction "2_2") (pintype "passive"))
    )
    (net (code "96") (name "Net-(IC10-D4+)") (class "Default")
      (node (ref "C26") (pin "1") (pinfunction "1_1") (pintype "passive"))
      (node (ref "IC10") (pin "24") (pinfunction "D4+_24") (pintype "bidirectional"))
      (node (ref "R21") (pin "2") (pinfunction "2_2") (pintype "passive"))
    )
    (net (code "97") (name "Net-(IC10-D4-)") (class "Default")
      (node (ref "C25") (pin "1") (pinfunction "1_1") (pintype "passive"))
      (node (ref "IC10") (pin "23") (pinfunction "D4-_23") (pintype "bidirectional"))
      (node (ref "R20") (pin "2") (pinfunction "2_2") (pintype "passive"))
    )
    (net (code "98") (name "Net-(IC10-XTAL1)") (class "Default")
      (node (ref "IC10") (pin "30") (pinfunction "XTAL1_30") (pintype "bidirectional"))
      (node (ref "Y2") (pin "3") (pinfunction "3_3") (pintype "passive"))
    )
    (net (code "99") (name "Net-(IC10-XTAL2)") (class "Default")
      (node (ref "IC10") (pin "29") (pinfunction "XTAL2_29") (pintype "bidirectional"))
      (node (ref "Y2") (pin "1") (pinfunction "1_1") (pintype "passive"))
    )
    (net (code "100") (name "Net-(ISP2-RST)") (class "Default")
      (node (ref "ISP2") (pin "5") (pinfunction "RST_5") (pintype "output"))
      (node (ref "R32") (pin "1") (pinfunction "1_1") (pintype "passive"))
    )
    (net (code "101") (name "Net-(ISP3-RST)") (class "Default")
      (node (ref "ISP3") (pin "5") (pinfunction "RST_5") (pintype "output"))
      (node (ref "R33") (pin "1") (pinfunction "1_1") (pintype "passive"))
    )
    (net (code "102") (name "Net-(ISP4-RST)") (class "Default")
      (node (ref "ISP4") (pin "5") (pinfunction "RST_5") (pintype "output"))
      (node (ref "R38") (pin "1") (pinfunction "1_1") (pintype "passive"))
    )
    (net (code "103") (name "Net-(ISP5-RST)") (class "Default")
      (node (ref "ISP5") (pin "5") (pinfunction "RST_5") (pintype "output"))
      (node (ref "R39") (pin "1") (pinfunction "1_1") (pintype "passive"))
    )
    (net (code "104") (name "Net-(JP8-Pad1)") (class "Default")
      (node (ref "JP8") (pin "1") (pinfunction "1_1") (pintype "passive"))
      (node (ref "R12") (pin "2") (pinfunction "2_2") (pintype "passive"))
    )
    (net (code "105") (name "Net-(JP8-Pad2)") (class "Default")
      (node (ref "JP8") (pin "2") (pinfunction "2_2") (pintype "passive"))
      (node (ref "R13") (pin "2") (pinfunction "2_2") (pintype "passive"))
    )
    (net (code "106") (name "Net-(L2-2)") (class "Default")
      (node (ref "F3") (pin "1") (pinfunction "1_1") (pintype "passive"))
      (node (ref "L2") (pin "P$2") (pinfunction "2_P$2") (pintype "passive"))
    )
    (net (code "107") (name "Net-(L3-2)") (class "Default")
      (node (ref "F2") (pin "1") (pinfunction "1_1") (pintype "passive"))
      (node (ref "L3") (pin "P$2") (pinfunction "2_P$2") (pintype "passive"))
    )
    (net (code "108") (name "Net-(L4-2)") (class "Default")
      (node (ref "F1") (pin "1") (pinfunction "1_1") (pintype "passive"))
      (node (ref "L4") (pin "P$2") (pinfunction "2_P$2") (pintype "passive"))
    )
    (net (code "109") (name "Net-(LED3-PadC)") (class "Default")
      (node (ref "LED3") (pin "C") (pinfunction "C_C") (pintype "passive"))
      (node (ref "R34") (pin "1") (pinfunction "1_1") (pintype "passive"))
    )
    (net (code "110") (name "Net-(Q1-D)") (class "Default")
      (node (ref "JP14") (pin "1") (pinfunction "1_1") (pintype "passive"))
      (node (ref "Q1") (pin "3") (pinfunction "D_3") (pintype "bidirectional"))
    )
    (net (code "111") (name "Net-(Q2-D)") (class "Default")
      (node (ref "JP15") (pin "1") (pinfunction "1_1") (pintype "passive"))
      (node (ref "Q2") (pin "3") (pinfunction "D_3") (pintype "bidirectional"))
    )
    (net (code "112") (name "Net-(Q3-D)") (class "Default")
      (node (ref "JP16") (pin "1") (pinfunction "1_1") (pintype "passive"))
      (node (ref "Q3") (pin "3") (pinfunction "D_3") (pintype "bidirectional"))
    )
    (net (code "113") (name "Net-(U$2-1)") (class "Default")
      (node (ref "JP17") (pin "2") (pinfunction "2_2") (pintype "passive"))
      (node (ref "R15") (pin "1") (pinfunction "1_1") (pintype "passive"))
      (node (ref "R21") (pin "1") (pinfunction "1_1") (pintype "passive"))
      (node (ref "U$2") (pin "A") (pinfunction "1_A") (pintype "passive"))
    )
    (net (code "114") (name "Net-(U$2-2)") (class "Default")
      (node (ref "JP17") (pin "3") (pinfunction "3_3") (pintype "passive"))
      (node (ref "R14") (pin "1") (pinfunction "1_1") (pintype "passive"))
      (node (ref "R20") (pin "1") (pinfunction "1_1") (pintype "passive"))
      (node (ref "U$2") (pin "C") (pinfunction "2_C") (pintype "passive"))
    )
    (net (code "115") (name "Net-(U$3-1)") (class "Default")
      (node (ref "JP13") (pin "2") (pinfunction "2_2") (pintype "passive"))
      (node (ref "R18") (pin "1") (pinfunction "1_1") (pintype "passive"))
      (node (ref "R23") (pin "1") (pinfunction "1_1") (pintype "passive"))
      (node (ref "U$3") (pin "A") (pinfunction "1_A") (pintype "passive"))
    )
    (net (code "116") (name "Net-(U$3-2)") (class "Default")
      (node (ref "JP13") (pin "3") (pinfunction "3_3") (pintype "passive"))
      (node (ref "R19") (pin "1") (pinfunction "1_1") (pintype "passive"))
      (node (ref "R22") (pin "1") (pinfunction "1_1") (pintype "passive"))
      (node (ref "U$3") (pin "C") (pinfunction "2_C") (pintype "passive"))
    )
    (net (code "117") (name "Net-(U$4-1)") (class "Default")
      (node (ref "JP11") (pin "2") (pinfunction "2_2") (pintype "passive"))
      (node (ref "R16") (pin "1") (pinfunction "1_1") (pintype "passive"))
      (node (ref "R25") (pin "1") (pinfunction "1_1") (pintype "passive"))
      (node (ref "U$4") (pin "A") (pinfunction "1_A") (pintype "passive"))
    )
    (net (code "118") (name "Net-(U$4-2)") (class "Default")
      (node (ref "JP11") (pin "3") (pinfunction "3_3") (pintype "passive"))
      (node (ref "R17") (pin "1") (pinfunction "1_1") (pintype "passive"))
      (node (ref "R24") (pin "1") (pinfunction "1_1") (pintype "passive"))
      (node (ref "U$4") (pin "C") (pinfunction "2_C") (pintype "passive"))
    )
    (net (code "119") (name "Net-(U$6-2)") (class "Default")
      (node (ref "C53") (pin "+") (pinfunction "+_+") (pintype "passive"))
      (node (ref "F7") (pin "1") (pinfunction "1_1") (pintype "bidirectional"))
      (node (ref "JP14") (pin "2") (pinfunction "2_2") (pintype "passive"))
      (node (ref "JP7") (pin "1") (pinfunction "1_1") (pintype "passive"))
      (node (ref "U$6") (pin "C") (pinfunction "2_C") (pintype "passive"))
    )
    (net (code "120") (name "Net-(U$7-2)") (class "Default")
      (node (ref "C54") (pin "+") (pinfunction "+_+") (pintype "passive"))
      (node (ref "F5") (pin "1") (pinfunction "1_1") (pintype "bidirectional"))
      (node (ref "JP15") (pin "2") (pinfunction "2_2") (pintype "passive"))
      (node (ref "JP9") (pin "1") (pinfunction "1_1") (pintype "passive"))
      (node (ref "U$7") (pin "C") (pinfunction "2_C") (pintype "passive"))
    )
    (net (code "121") (name "Net-(U$8-2)") (class "Default")
      (node (ref "C55") (pin "+") (pinfunction "+_+") (pintype "passive"))
      (node (ref "F6") (pin "1") (pinfunction "1_1") (pintype "bidirectional"))
      (node (ref "JP10") (pin "1") (pinfunction "1_1") (pintype "passive"))
      (node (ref "JP16") (pin "2") (pinfunction "2_2") (pintype "passive"))
      (node (ref "U$8") (pin "C") (pinfunction "2_C") (pintype "passive"))
    )
    (net (code "122") (name "Net-(U3-PB6(XTAL1{slash}TOSC1))") (class "Default")
      (node (ref "U3") (pin "7") (pinfunction "PB6(XTAL1/TOSC1)_7") (pintype "bidirectional"))
      (node (ref "Y1") (pin "1") (pinfunction "1_1") (pintype "passive"))
    )
    (net (code "123") (name "Net-(U3-PB7(XTAL2{slash}TOSC2))") (class "Default")
      (node (ref "U3") (pin "8") (pinfunction "PB7(XTAL2/TOSC2)_8") (pintype "bidirectional"))
      (node (ref "Y1") (pin "3") (pinfunction "3_3") (pintype "passive"))
    )
    (net (code "124") (name "unconnected-(IC3-QH*-Pad9)") (class "Default")
      (node (ref "IC3") (pin "9") (pinfunction "QH*_9") (pintype "tri_state"))
    )
    (net (code "125") (name "unconnected-(IC4-CBUS0-Pad15)") (class "Default")
      (node (ref "IC4") (pin "15") (pinfunction "CBUS0_15") (pintype "bidirectional"))
    )
    (net (code "126") (name "unconnected-(IC4-CBUS1-Pad14)") (class "Default")
      (node (ref "IC4") (pin "14") (pinfunction "CBUS1_14") (pintype "bidirectional"))
    )
    (net (code "127") (name "unconnected-(IC4-CBUS2-Pad7)") (class "Default")
      (node (ref "IC4") (pin "7") (pinfunction "CBUS2_7") (pintype "bidirectional"))
    )
    (net (code "128") (name "unconnected-(IC4-CBUS3-Pad16)") (class "Default")
      (node (ref "IC4") (pin "16") (pinfunction "CBUS3_16") (pintype "bidirectional"))
    )
    (net (code "129") (name "unconnected-(IC4-~{CTS}-Pad6)") (class "Default")
      (node (ref "IC4") (pin "6") (pinfunction "~{CTS}_6") (pintype "bidirectional"))
    )
    (net (code "130") (name "unconnected-(IC5-STAT4-Pad11)") (class "Default")
      (node (ref "IC5") (pin "11") (pinfunction "STAT4_11") (pintype "bidirectional"))
    )
    (net (code "131") (name "unconnected-(IC6-STAT4-Pad11)") (class "Default")
      (node (ref "IC6") (pin "11") (pinfunction "STAT4_11") (pintype "bidirectional"))
    )
    (net (code "132") (name "unconnected-(IC7-STAT4-Pad11)") (class "Default")
      (node (ref "IC7") (pin "11") (pinfunction "STAT4_11") (pintype "bidirectional"))
    )
    (net (code "133") (name "unconnected-(IC8-STAT4-Pad11)") (class "Default")
      (node (ref "IC8") (pin "11") (pinfunction "STAT4_11") (pintype "bidirectional"))
    )
    (net (code "134") (name "unconnected-(IC9-STAT4-Pad11)") (class "Default")
      (node (ref "IC9") (pin "11") (pinfunction "STAT4_11") (pintype "bidirectional"))
    )
    (net (code "135") (name "unconnected-(IC10-EECLK-Pad5)") (class "Default")
      (node (ref "IC10") (pin "5") (pinfunction "EECLK_5") (pintype "bidirectional"))
    )
    (net (code "136") (name "unconnected-(IC10-SUSPND-Pad32)") (class "Default")
      (node (ref "IC10") (pin "32") (pinfunction "SUSPND_32") (pintype "bidirectional"))
    )
    (net (code "137") (name "unconnected-(IC10-~{PWRON1}-Pad9)") (class "Default")
      (node (ref "IC10") (pin "9") (pinfunction "~{PWRON1}_9") (pintype "bidirectional"))
    )
    (net (code "138") (name "unconnected-(IC10-~{PWRON2}-Pad13)") (class "Default")
      (node (ref "IC10") (pin "13") (pinfunction "~{PWRON2}_13") (pintype "bidirectional"))
    )
    (net (code "139") (name "unconnected-(IC10-~{PWRON3}-Pad17)") (class "Default")
      (node (ref "IC10") (pin "17") (pinfunction "~{PWRON3}_17") (pintype "bidirectional"))
    )
    (net (code "140") (name "unconnected-(IC10-~{PWRON4}-Pad21)") (class "Default")
      (node (ref "IC10") (pin "21") (pinfunction "~{PWRON4}_21") (pintype "bidirectional"))
    )
    (net (code "141") (name "unconnected-(U2-BP-Pad4)") (class "Default")
      (node (ref "U2") (pin "4") (pinfunction "BP_4") (pintype "input"))
    )
  )
)
